# BLDC_Controller.net
KiCad netlist of a schematic drawn in EAGLE
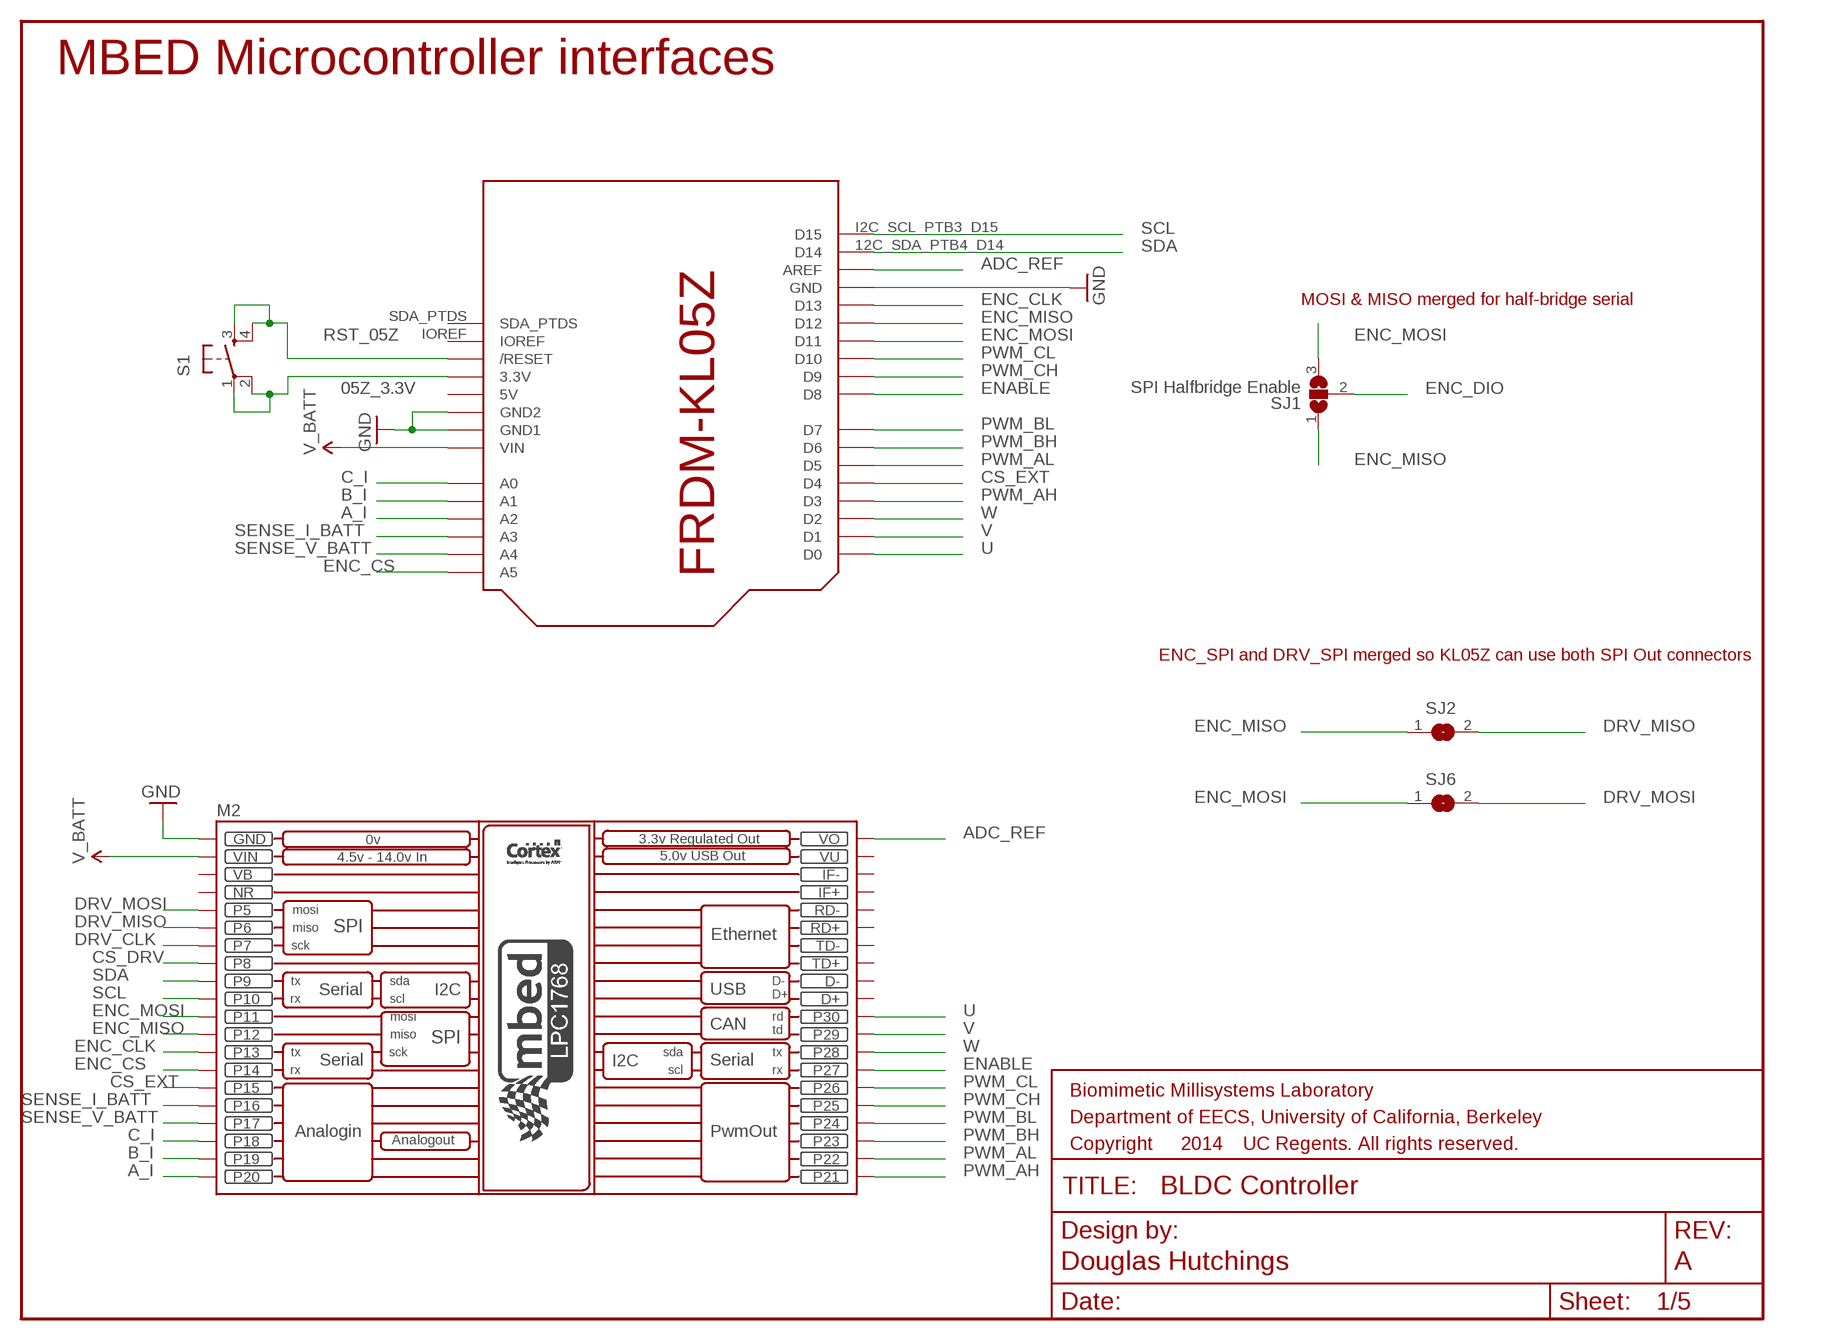
[diagram p0: schematic, sheet 1]
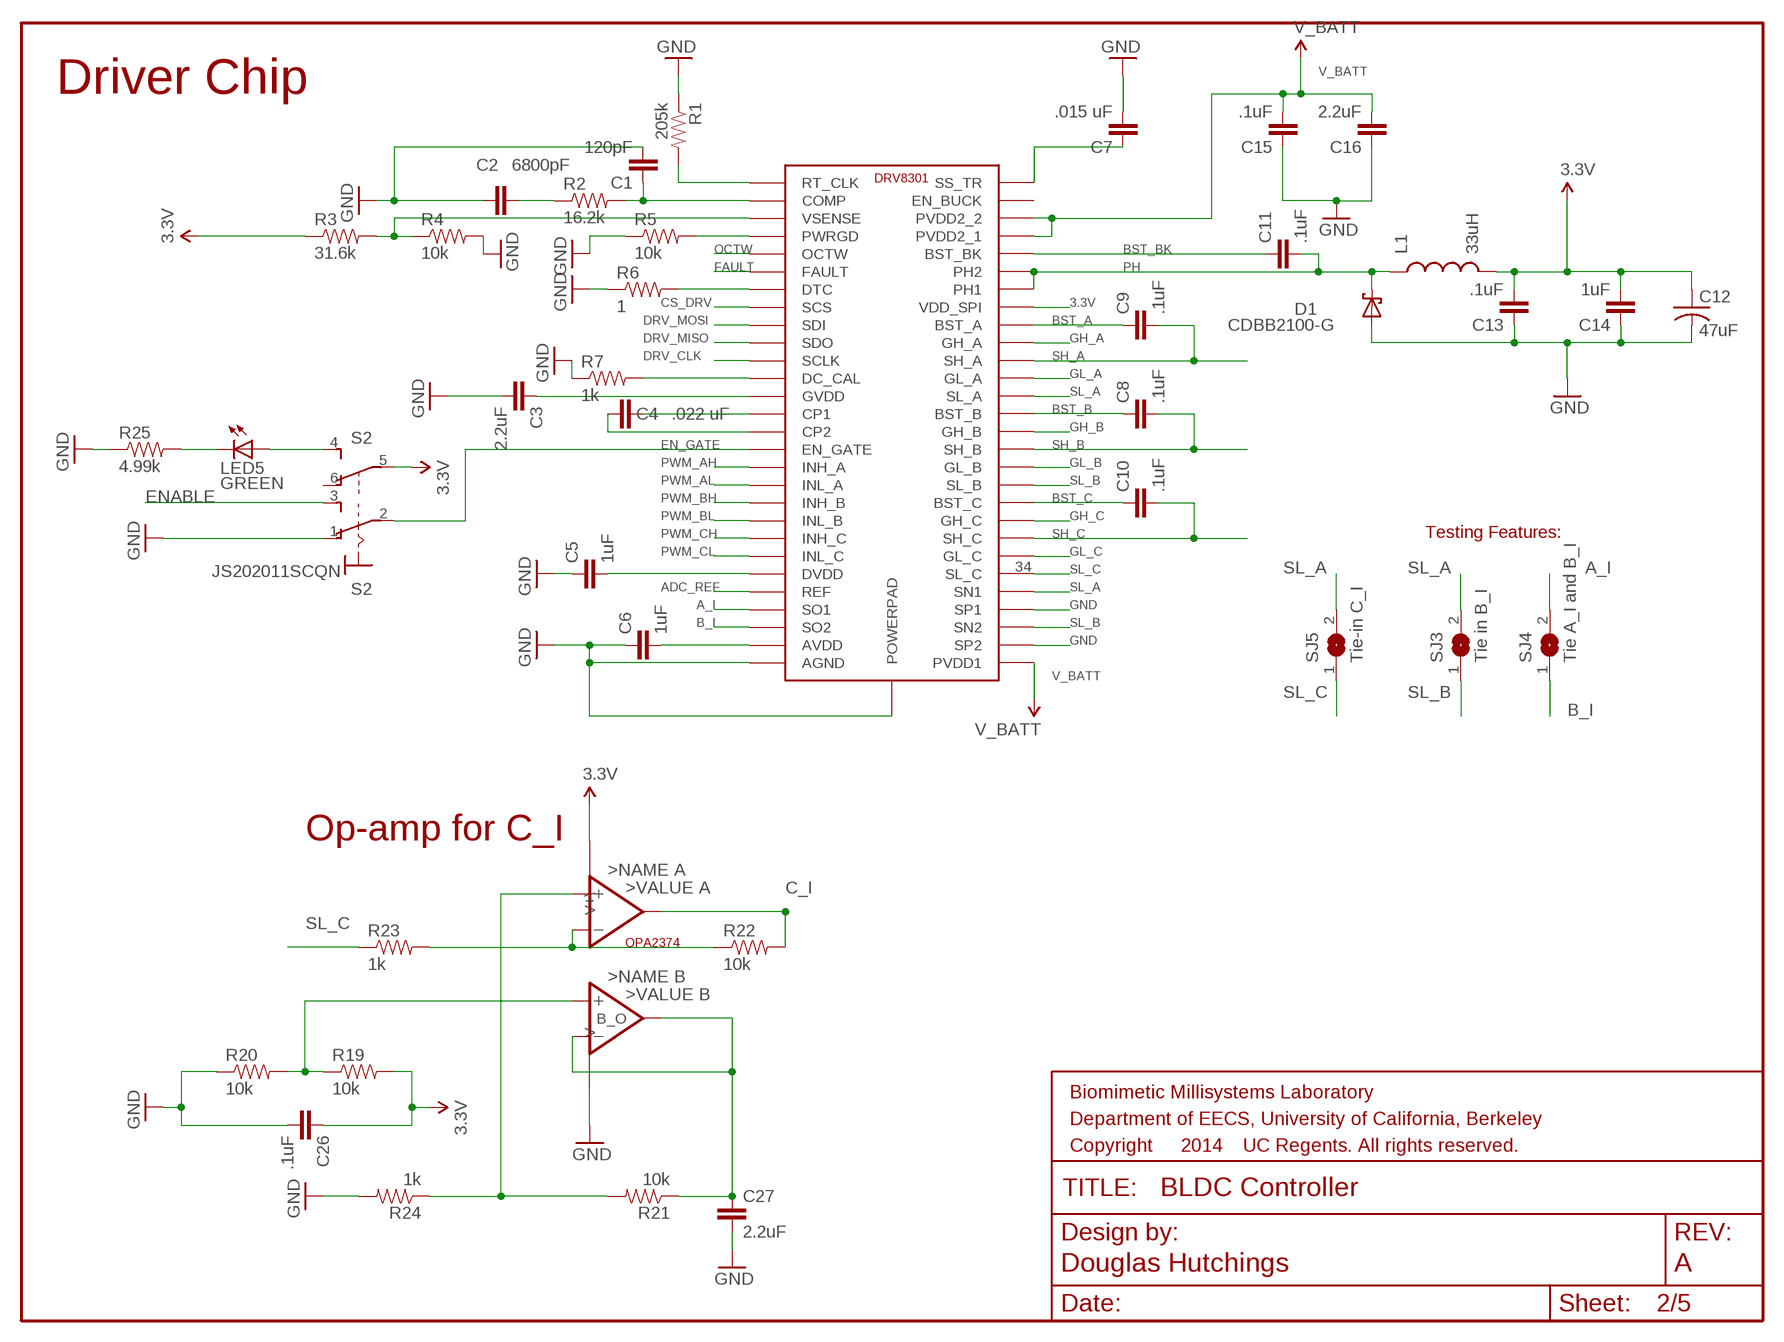
[diagram p1: schematic, sheet 2]
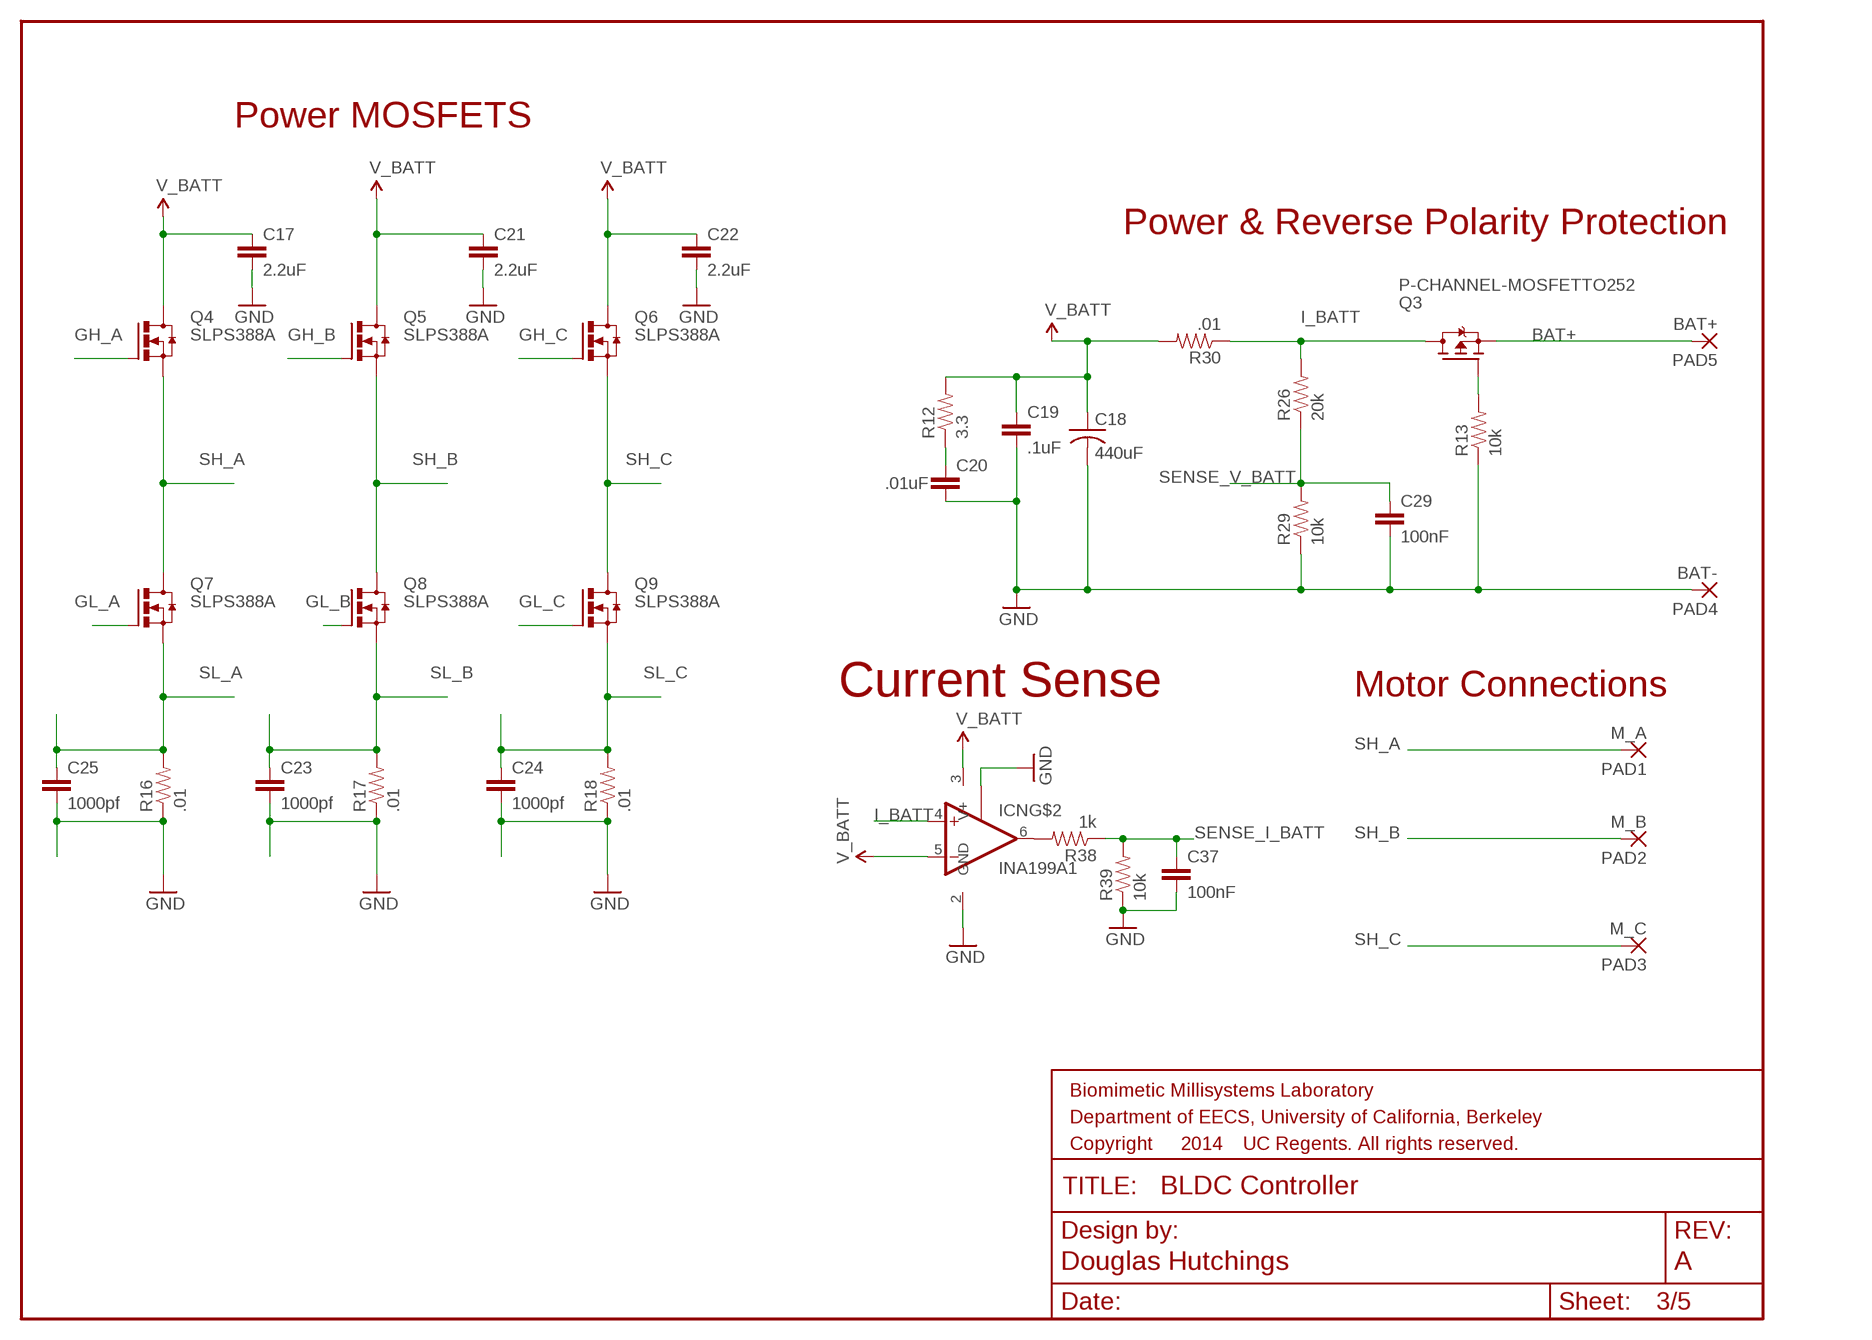
[diagram p2: schematic, sheet 3]
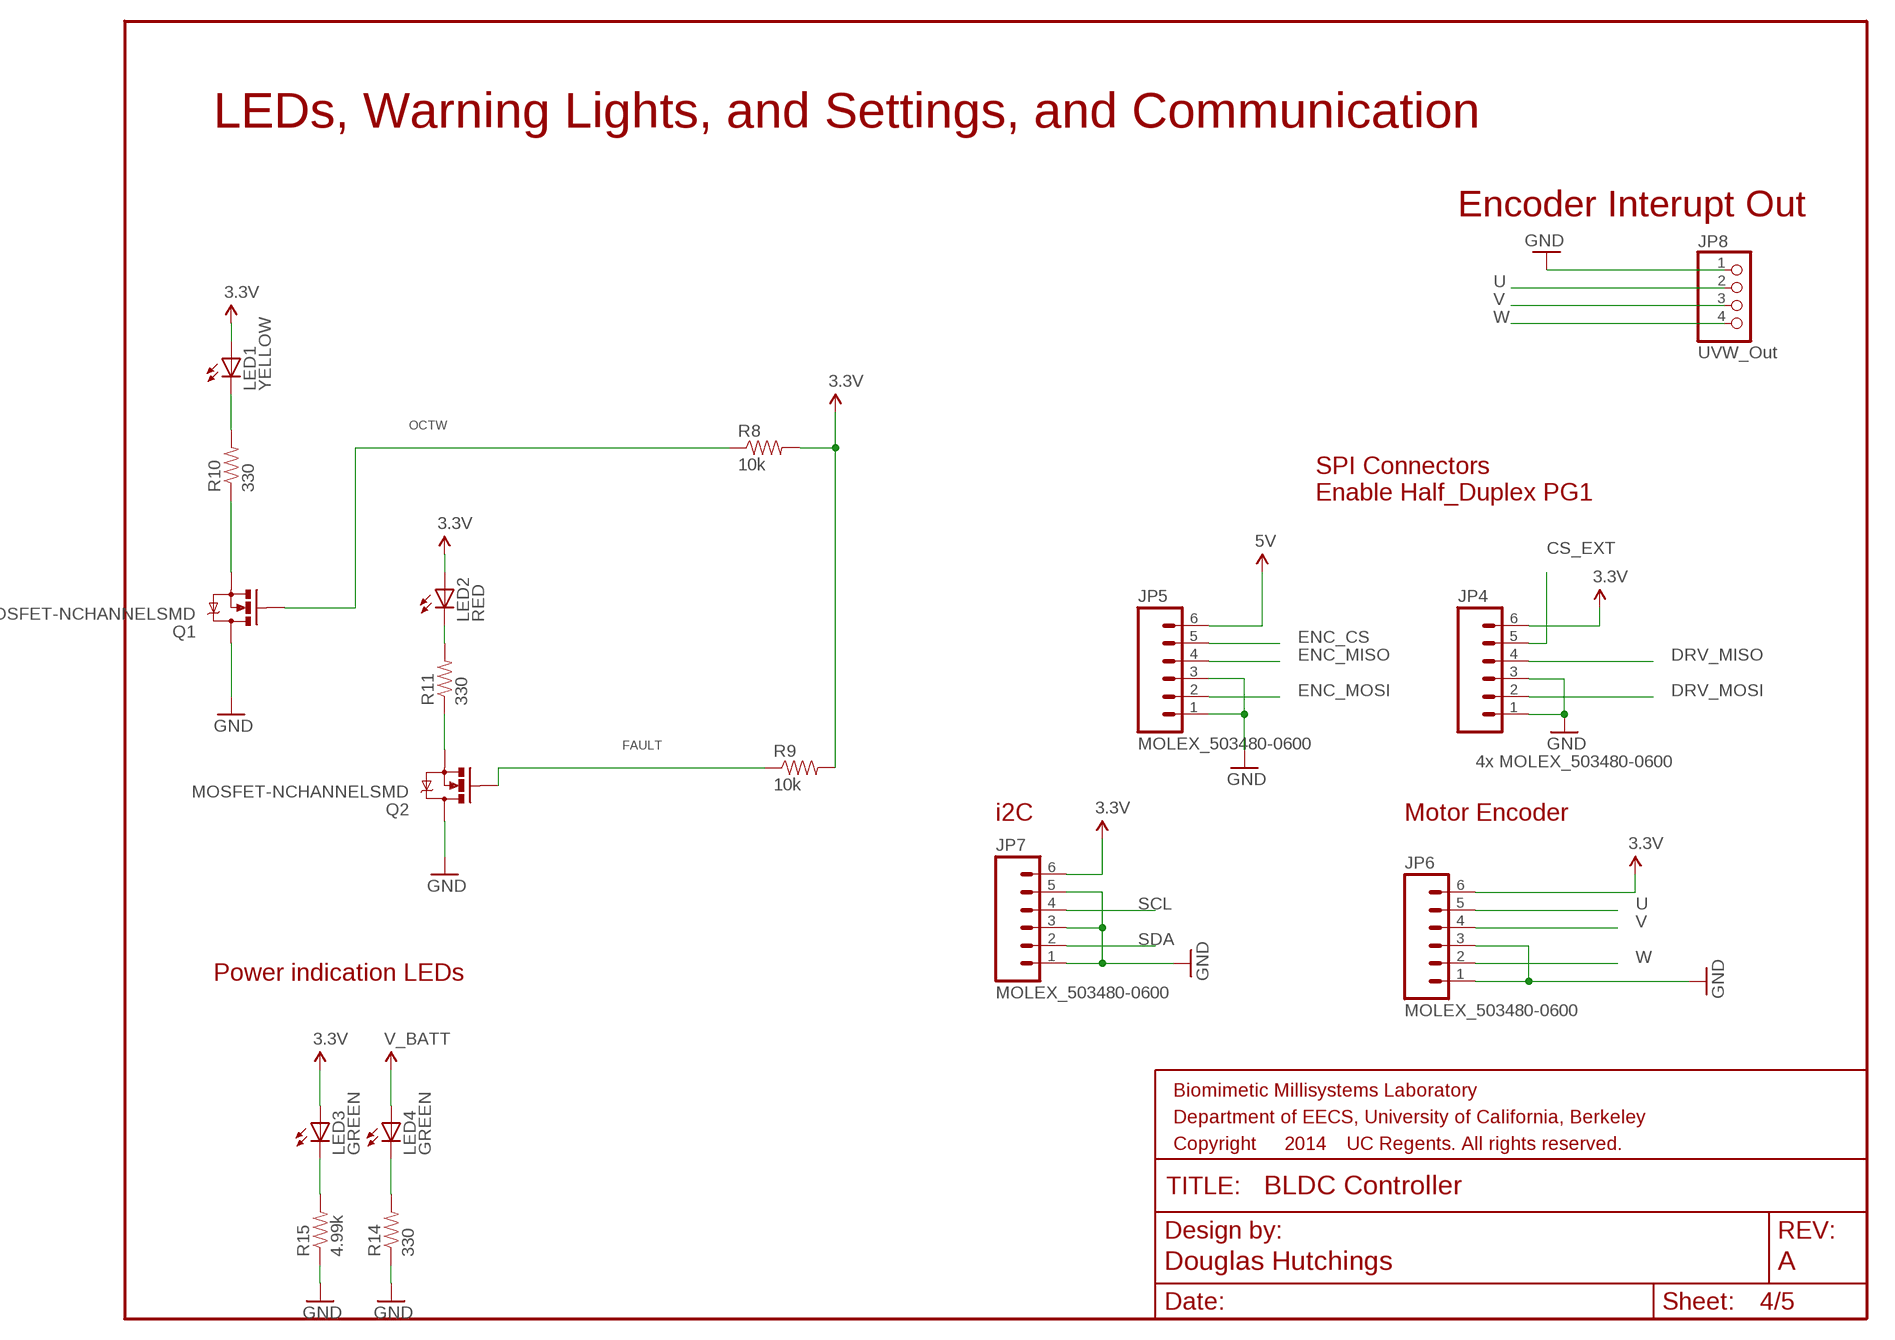
[diagram p3: schematic, sheet 4]
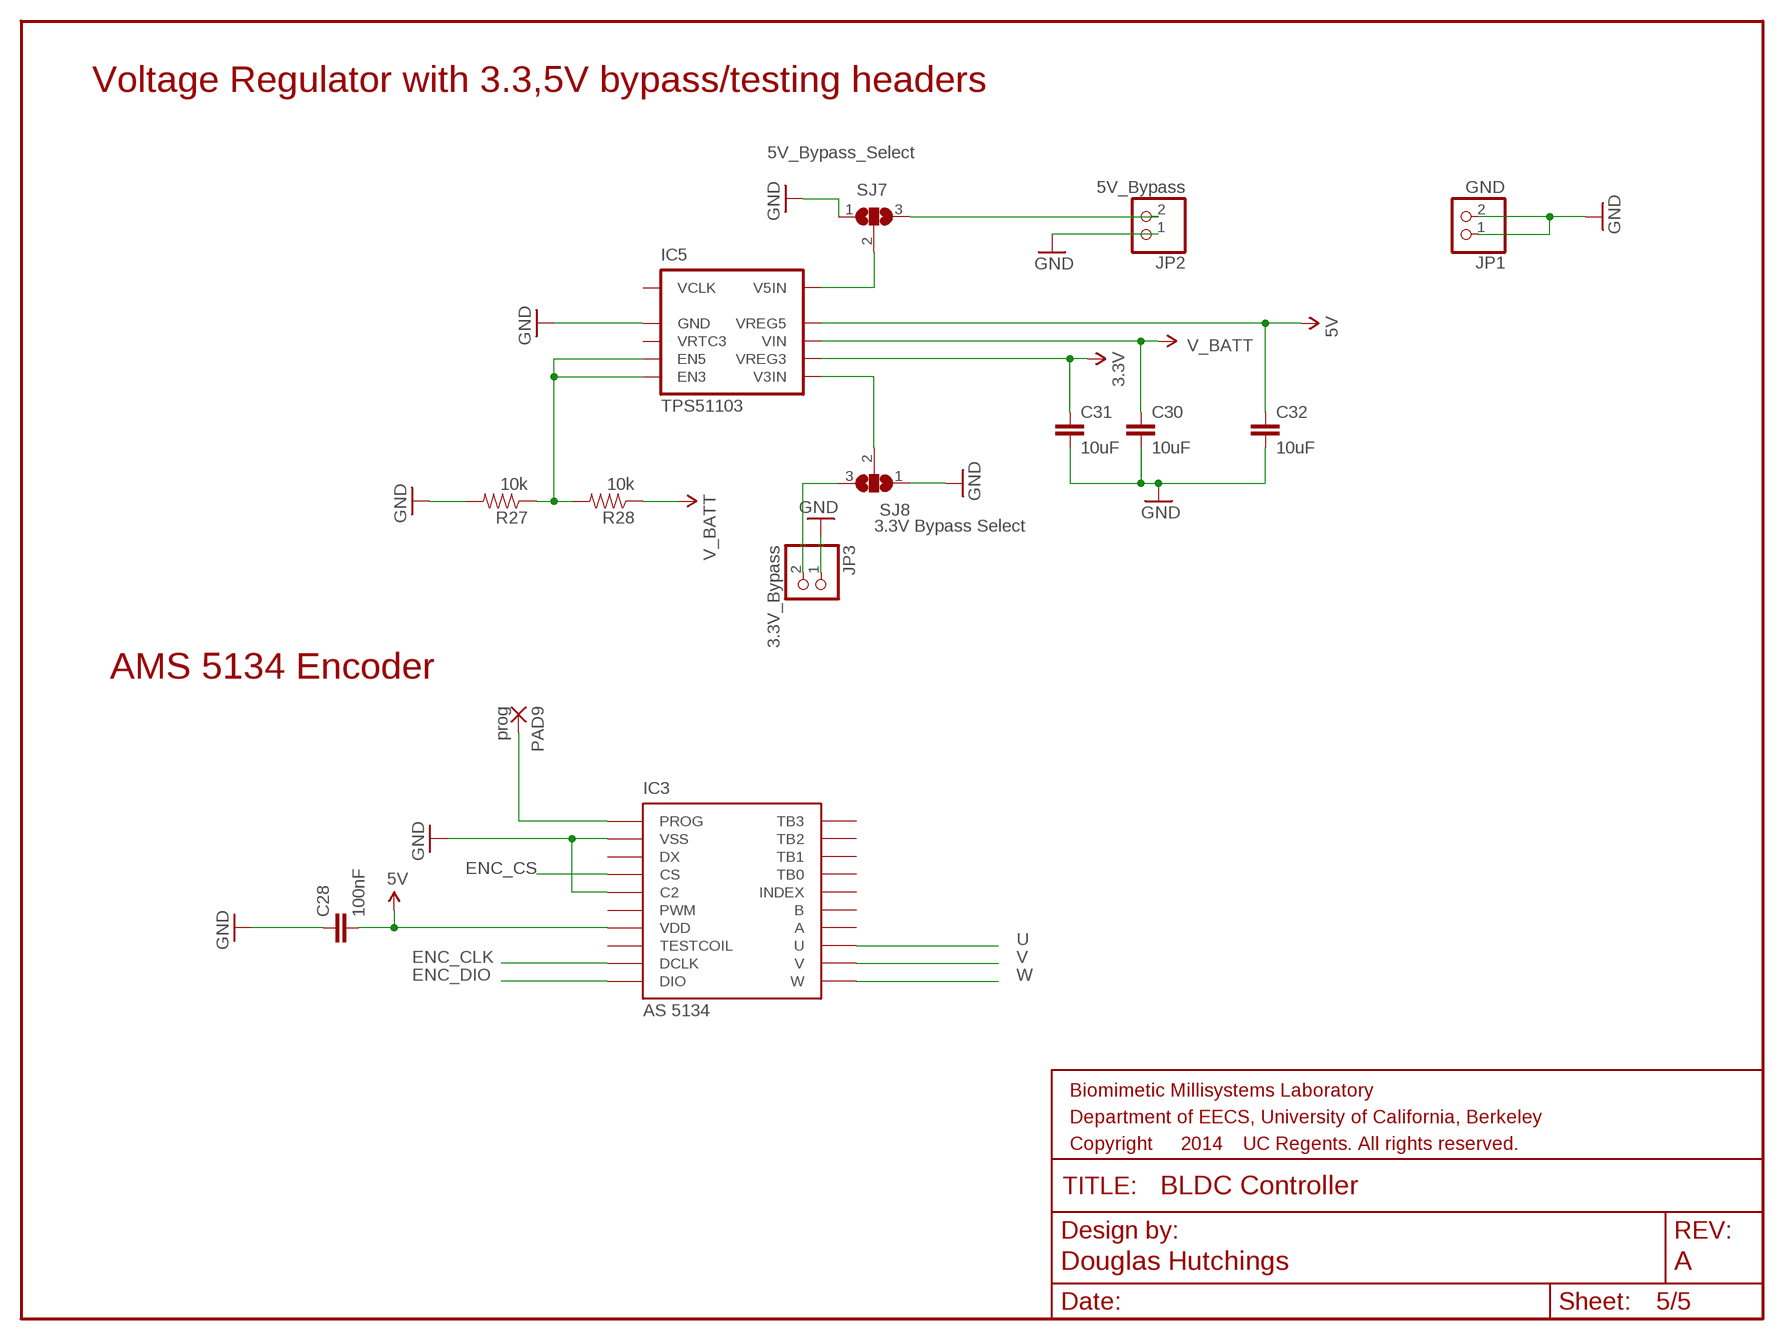
[diagram p4: schematic, sheet 5]

(export (version "E")
  (design (tool "Eeschema 10.0.6"))
  (components
    (comp (ref "M1")
      (value "FRDM-KL05Z")
      (footprint "eagle-import:FREESCALEKL05Z")
      (libsource (lib "eagle-import") (part "FRDM-KL05Z"))
    )
    (comp (ref "M2")
      (value "MBED_NXP_LPC1768")
      (footprint "eagle-import:MBED-KIT")
      (libsource (lib "eagle-import") (part "MBED_NXP_LPC1768"))
    )
    (comp (ref "S1")
      (value "TAC_SWITCHPTH")
      (footprint "eagle-import:TACTILE-PTH")
      (libsource (lib "eagle-import") (part "TAC_SWITCHPTH"))
    )
    (comp (ref "SJ1")
      (value "SPI Halfbridge Enable")
      (footprint "eagle-import:SJ_2")
      (libsource (lib "eagle-import") (part "SJ2W"))
    )
    (comp (ref "SJ2") (value "SJ") (footprint "eagle-import:SJ") (libsource (lib "eagle-import") (part "SJ")))
    (comp (ref "SJ6") (value "SJ") (footprint "eagle-import:SJ") (libsource (lib "eagle-import") (part "SJ")))
    (comp (ref "C28")
      (value "100nF")
      (footprint "eagle-import:0402-CAP")
      (libsource (lib "eagle-import") (part "CAP0402-CAP"))
    )
    (comp (ref "C30")
      (value "10uF")
      (footprint "eagle-import:0603-CAP")
      (libsource (lib "eagle-import") (part "CAP0603-CAP"))
    )
    (comp (ref "C31")
      (value "10uF")
      (footprint "eagle-import:0603-CAP")
      (libsource (lib "eagle-import") (part "CAP0603-CAP"))
    )
    (comp (ref "C32")
      (value "10uF")
      (footprint "eagle-import:0603-CAP")
      (libsource (lib "eagle-import") (part "CAP0603-CAP"))
    )
    (comp (ref "IC3")
      (value "AS 5134")
      (footprint "eagle-import:AS5134")
      (libsource (lib "eagle-import") (part "AS5134"))
    )
    (comp (ref "IC5")
      (value "TPS51103")
      (footprint "eagle-import:DRC(S-PVSON-N10)")
      (libsource (lib "eagle-import") (part "TPS51103"))
    )
    (comp (ref "JP1")
      (value "GND")
      (footprint "eagle-import:1X02")
      (libsource (lib "eagle-import") (part "PINHD-1X2"))
    )
    (comp (ref "JP2")
      (value "5V_Bypass")
      (footprint "eagle-import:1X02")
      (libsource (lib "eagle-import") (part "PINHD-1X2"))
    )
    (comp (ref "JP3")
      (value "3.3V_Bypass")
      (footprint "eagle-import:1X02")
      (libsource (lib "eagle-import") (part "PINHD-1X2"))
    )
    (comp (ref "PAD9")
      (value "prog")
      (footprint "eagle-import:SMD1,27-2,54")
      (libsource (lib "eagle-import") (part "SMD2"))
    )
    (comp (ref "R27")
      (value "10k")
      (footprint "eagle-import:0402-RES")
      (libsource (lib "eagle-import") (part "RESISTOR0402-RES"))
    )
    (comp (ref "R28")
      (value "10k")
      (footprint "eagle-import:0402-RES")
      (libsource (lib "eagle-import") (part "RESISTOR0402-RES"))
    )
    (comp (ref "SJ7")
      (value "5V_Bypass_Select")
      (footprint "eagle-import:SJ_2")
      (libsource (lib "eagle-import") (part "SJ2W"))
    )
    (comp (ref "SJ8")
      (value "3.3V Bypass Select")
      (footprint "eagle-import:SJ_2")
      (libsource (lib "eagle-import") (part "SJ2W"))
    )
    (comp (ref "C17")
      (value "2.2uF")
      (footprint "eagle-import:0603-CAP")
      (libsource (lib "eagle-import") (part "CAP0603-CAP"))
    )
    (comp (ref "C18")
      (value "440uF")
      (footprint "eagle-import:C1210")
      (libsource (lib "eagle-import") (part "C-USC1210"))
    )
    (comp (ref "C19")
      (value ".1uF")
      (footprint "eagle-import:0402-CAP")
      (libsource (lib "eagle-import") (part "CAP0402-CAP"))
    )
    (comp (ref "C20")
      (value ".01uF")
      (footprint "eagle-import:0402-CAP")
      (libsource (lib "eagle-import") (part "CAP0402-CAP"))
    )
    (comp (ref "C21")
      (value "2.2uF")
      (footprint "eagle-import:0603-CAP")
      (libsource (lib "eagle-import") (part "CAP0603-CAP"))
    )
    (comp (ref "C22")
      (value "2.2uF")
      (footprint "eagle-import:0603-CAP")
      (libsource (lib "eagle-import") (part "CAP0603-CAP"))
    )
    (comp (ref "C23")
      (value "1000pf")
      (footprint "eagle-import:0603-CAP")
      (libsource (lib "eagle-import") (part "CAP0603-CAP"))
    )
    (comp (ref "C24")
      (value "1000pf")
      (footprint "eagle-import:0603-CAP")
      (libsource (lib "eagle-import") (part "CAP0603-CAP"))
    )
    (comp (ref "C25")
      (value "1000pf")
      (footprint "eagle-import:0603-CAP")
      (libsource (lib "eagle-import") (part "CAP0603-CAP"))
    )
    (comp (ref "C29")
      (value "100nF")
      (footprint "eagle-import:0402-CAP")
      (libsource (lib "eagle-import") (part "CAP0402-CAP"))
    )
    (comp (ref "C37")
      (value "100nF")
      (footprint "eagle-import:0402-CAP")
      (libsource (lib "eagle-import") (part "CAP0402-CAP"))
    )
    (comp (ref "ICN")
      (value "INA199A1")
      (footprint "eagle-import:SC70-6")
      (libsource (lib "eagle-import") (part "INA199A1"))
    )
    (comp (ref "PAD1")
      (value "M_A")
      (footprint "eagle-import:SMD1,27-2,54")
      (libsource (lib "eagle-import") (part "SMD2"))
    )
    (comp (ref "PAD2")
      (value "M_B")
      (footprint "eagle-import:SMD1,27-2,54")
      (libsource (lib "eagle-import") (part "SMD2"))
    )
    (comp (ref "PAD3")
      (value "M_C")
      (footprint "eagle-import:SMD1,27-2,54")
      (libsource (lib "eagle-import") (part "SMD2"))
    )
    (comp (ref "PAD4")
      (value "BAT-")
      (footprint "eagle-import:SMD1,27-2,54")
      (libsource (lib "eagle-import") (part "SMD2"))
    )
    (comp (ref "PAD5")
      (value "BAT+")
      (footprint "eagle-import:SMD1,27-2,54")
      (libsource (lib "eagle-import") (part "SMD2"))
    )
    (comp (ref "Q3")
      (value "P-CHANNEL-MOSFETTO252")
      (footprint "eagle-import:TO252")
      (libsource (lib "eagle-import") (part "P-CHANNEL-MOSFETTO252"))
    )
    (comp (ref "Q4")
      (value "SLPS388A")
      (footprint "eagle-import:SLPS388A")
      (libsource (lib "eagle-import") (part "SLPS388A"))
    )
    (comp (ref "Q5")
      (value "SLPS388A")
      (footprint "eagle-import:SLPS388A")
      (libsource (lib "eagle-import") (part "SLPS388A"))
    )
    (comp (ref "Q6")
      (value "SLPS388A")
      (footprint "eagle-import:SLPS388A")
      (libsource (lib "eagle-import") (part "SLPS388A"))
    )
    (comp (ref "Q7")
      (value "SLPS388A")
      (footprint "eagle-import:SLPS388A")
      (libsource (lib "eagle-import") (part "SLPS388A"))
    )
    (comp (ref "Q8")
      (value "SLPS388A")
      (footprint "eagle-import:SLPS388A")
      (libsource (lib "eagle-import") (part "SLPS388A"))
    )
    (comp (ref "Q9")
      (value "SLPS388A")
      (footprint "eagle-import:SLPS388A")
      (libsource (lib "eagle-import") (part "SLPS388A"))
    )
    (comp (ref "R12")
      (value "3.3")
      (footprint "eagle-import:0402-RES")
      (libsource (lib "eagle-import") (part "RESISTOR0402-RES"))
    )
    (comp (ref "R13")
      (value "10k")
      (footprint "eagle-import:0603-RES")
      (libsource (lib "eagle-import") (part "RESISTOR0603-RES"))
    )
    (comp (ref "R16")
      (value ".01")
      (footprint "eagle-import:R2010")
      (libsource (lib "eagle-import") (part "RESISTOR2010"))
    )
    (comp (ref "R17")
      (value ".01")
      (footprint "eagle-import:R2010")
      (libsource (lib "eagle-import") (part "RESISTOR2010"))
    )
    (comp (ref "R18")
      (value ".01")
      (footprint "eagle-import:R2010")
      (libsource (lib "eagle-import") (part "RESISTOR2010"))
    )
    (comp (ref "R26")
      (value "20k")
      (footprint "eagle-import:0402-RES")
      (libsource (lib "eagle-import") (part "RESISTOR0402-RES"))
    )
    (comp (ref "R29")
      (value "10k")
      (footprint "eagle-import:0402-RES")
      (libsource (lib "eagle-import") (part "RESISTOR0402-RES"))
    )
    (comp (ref "R30")
      (value ".01")
      (footprint "eagle-import:R2010")
      (libsource (lib "eagle-import") (part "RESISTOR2010"))
    )
    (comp (ref "R38")
      (value "1k")
      (footprint "eagle-import:0402-RES")
      (libsource (lib "eagle-import") (part "RESISTOR0402-RES"))
    )
    (comp (ref "R39")
      (value "10k")
      (footprint "eagle-import:0402-RES")
      (libsource (lib "eagle-import") (part "RESISTOR0402-RES"))
    )
    (comp (ref "C1")
      (value "120pF")
      (footprint "eagle-import:0402-CAP")
      (libsource (lib "eagle-import") (part "CAP0402-CAP"))
    )
    (comp (ref "C2")
      (value "6800pF")
      (footprint "eagle-import:0402-CAP")
      (libsource (lib "eagle-import") (part "CAP0402-CAP"))
    )
    (comp (ref "C3")
      (value "2.2uF")
      (footprint "eagle-import:0402-CAP")
      (libsource (lib "eagle-import") (part "CAP0402-CAP"))
    )
    (comp (ref "C4")
      (value ".022 uF")
      (footprint "eagle-import:0402-CAP")
      (libsource (lib "eagle-import") (part "CAP0402-CAP"))
    )
    (comp (ref "C5")
      (value "1uF")
      (footprint "eagle-import:0402-CAP")
      (libsource (lib "eagle-import") (part "CAP0402-CAP"))
    )
    (comp (ref "C6")
      (value "1uF")
      (footprint "eagle-import:0402-CAP")
      (libsource (lib "eagle-import") (part "CAP0402-CAP"))
    )
    (comp (ref "C7")
      (value ".015 uF")
      (footprint "eagle-import:0402-CAP")
      (libsource (lib "eagle-import") (part "CAP0402-CAP"))
    )
    (comp (ref "C8")
      (value ".1uF")
      (footprint "eagle-import:0402-CAP")
      (libsource (lib "eagle-import") (part "CAP0402-CAP"))
    )
    (comp (ref "C9")
      (value ".1uF")
      (footprint "eagle-import:0402-CAP")
      (libsource (lib "eagle-import") (part "CAP0402-CAP"))
    )
    (comp (ref "C10")
      (value ".1uF")
      (footprint "eagle-import:0402-CAP")
      (libsource (lib "eagle-import") (part "CAP0402-CAP"))
    )
    (comp (ref "C11")
      (value ".1uF")
      (footprint "eagle-import:0402-CAP")
      (libsource (lib "eagle-import") (part "CAP0402-CAP"))
    )
    (comp (ref "C12")
      (value "47uF")
      (footprint "eagle-import:C0603")
      (libsource (lib "eagle-import") (part "C-USC0603"))
    )
    (comp (ref "C13")
      (value ".1uF")
      (footprint "eagle-import:0402-CAP")
      (libsource (lib "eagle-import") (part "CAP0402-CAP"))
    )
    (comp (ref "C14")
      (value "1uF")
      (footprint "eagle-import:0402-CAP")
      (libsource (lib "eagle-import") (part "CAP0402-CAP"))
    )
    (comp (ref "C15")
      (value ".1uF")
      (footprint "eagle-import:0402-CAP")
      (libsource (lib "eagle-import") (part "CAP0402-CAP"))
    )
    (comp (ref "C16")
      (value "2.2uF")
      (footprint "eagle-import:0402-CAP")
      (libsource (lib "eagle-import") (part "CAP0402-CAP"))
    )
    (comp (ref "C26")
      (value ".1uF")
      (footprint "eagle-import:0402-CAP")
      (libsource (lib "eagle-import") (part "CAP0402-CAP"))
    )
    (comp (ref "C27")
      (value "2.2uF")
      (footprint "eagle-import:0402-CAP")
      (libsource (lib "eagle-import") (part "CAP0402-CAP"))
    )
    (comp (ref "D1")
      (value "CDBB2100-G")
      (footprint "eagle-import:SMB")
      (libsource (lib "eagle-import") (part "SCHOTTKY-DIODESMD"))
    )
    (comp (ref "IC1")
      (value "DRV8301")
      (footprint "eagle-import:DRV8301")
      (libsource (lib "eagle-import") (part "DRV8301"))
    )
    (comp (ref "IC2")
      (value "OPA2374")
      (footprint "eagle-import:SOT-23")
      (libsource (lib "eagle-import") (part "OPA2374"))
    )
    (comp (ref "L1")
      (value "33uH")
      (footprint "eagle-import:0805")
      (libsource (lib "eagle-import") (part "INDUCTOR0805"))
    )
    (comp (ref "LED5")
      (value "GREEN")
      (footprint "eagle-import:LED-0603")
      (libsource (lib "eagle-import") (part "LED0603"))
    )
    (comp (ref "R1")
      (value "205k")
      (footprint "eagle-import:0402-RES")
      (libsource (lib "eagle-import") (part "RESISTOR0402-RES"))
    )
    (comp (ref "R2")
      (value "16.2k")
      (footprint "eagle-import:0402-RES")
      (libsource (lib "eagle-import") (part "RESISTOR0402-RES"))
    )
    (comp (ref "R3")
      (value "31.6k")
      (footprint "eagle-import:0402-RES")
      (libsource (lib "eagle-import") (part "RESISTOR0402-RES"))
    )
    (comp (ref "R4")
      (value "10k")
      (footprint "eagle-import:0402-RES")
      (libsource (lib "eagle-import") (part "RESISTOR0402-RES"))
    )
    (comp (ref "R5")
      (value "10k")
      (footprint "eagle-import:0402-RES")
      (libsource (lib "eagle-import") (part "RESISTOR0402-RES"))
    )
    (comp (ref "R6")
      (value "1")
      (footprint "eagle-import:0402-RES")
      (libsource (lib "eagle-import") (part "RESISTOR0402-RES"))
    )
    (comp (ref "R7")
      (value "1k")
      (footprint "eagle-import:0402-RES")
      (libsource (lib "eagle-import") (part "RESISTOR0402-RES"))
    )
    (comp (ref "R19")
      (value "10k")
      (footprint "eagle-import:0402-RES")
      (libsource (lib "eagle-import") (part "RESISTOR0402-RES"))
    )
    (comp (ref "R20")
      (value "10k")
      (footprint "eagle-import:0402-RES")
      (libsource (lib "eagle-import") (part "RESISTOR0402-RES"))
    )
    (comp (ref "R21")
      (value "10k")
      (footprint "eagle-import:0402-RES")
      (libsource (lib "eagle-import") (part "RESISTOR0402-RES"))
    )
    (comp (ref "R22")
      (value "10k")
      (footprint "eagle-import:0402-RES")
      (libsource (lib "eagle-import") (part "RESISTOR0402-RES"))
    )
    (comp (ref "R23")
      (value "1k")
      (footprint "eagle-import:0402-RES")
      (libsource (lib "eagle-import") (part "RESISTOR0402-RES"))
    )
    (comp (ref "R24")
      (value "1k")
      (footprint "eagle-import:0402-RES")
      (libsource (lib "eagle-import") (part "RESISTOR0402-RES"))
    )
    (comp (ref "R25")
      (value "4.99k")
      (footprint "eagle-import:0603-RES")
      (libsource (lib "eagle-import") (part "RESISTOR0603-RES"))
    )
    (comp (ref "S2")
      (value "JS202011SCQN")
      (footprint "eagle-import:JS202011SCQN")
      (libsource (lib "eagle-import") (part "JS202011SCQN"))
    )
    (comp (ref "SJ3")
      (value "Tie in B_I")
      (footprint "eagle-import:SJ")
      (libsource (lib "eagle-import") (part "SJ"))
    )
    (comp (ref "SJ4")
      (value "Tie A_I and B_I")
      (footprint "eagle-import:SJ")
      (libsource (lib "eagle-import") (part "SJ"))
    )
    (comp (ref "SJ5")
      (value "Tie-in C_I")
      (footprint "eagle-import:SJ")
      (libsource (lib "eagle-import") (part "SJ"))
    )
    (comp (ref "JP4")
      (value "4x MOLEX_503480-0600")
      (footprint "eagle-import:MOLEX_503480-0600")
      (libsource (lib "eagle-import") (part "MOLEX_503480-0600"))
    )
    (comp (ref "JP5")
      (value "MOLEX_503480-0600")
      (footprint "eagle-import:MOLEX_503480-0600")
      (libsource (lib "eagle-import") (part "MOLEX_503480-0600"))
    )
    (comp (ref "JP6")
      (value "MOLEX_503480-0600")
      (footprint "eagle-import:MOLEX_503480-0600")
      (libsource (lib "eagle-import") (part "MOLEX_503480-0600"))
    )
    (comp (ref "JP7")
      (value "MOLEX_503480-0600")
      (footprint "eagle-import:MOLEX_503480-0600")
      (libsource (lib "eagle-import") (part "MOLEX_503480-0600"))
    )
    (comp (ref "JP8")
      (value "UVW_Out")
      (footprint "eagle-import:1X04")
      (libsource (lib "eagle-import") (part "PINHD-1X4"))
    )
    (comp (ref "LED1")
      (value "YELLOW")
      (footprint "eagle-import:LED-0603")
      (libsource (lib "eagle-import") (part "LED0603"))
    )
    (comp (ref "LED2")
      (value "RED")
      (footprint "eagle-import:LED-0603")
      (libsource (lib "eagle-import") (part "LED0603"))
    )
    (comp (ref "LED3")
      (value "GREEN")
      (footprint "eagle-import:LED-0603")
      (libsource (lib "eagle-import") (part "LED0603"))
    )
    (comp (ref "LED4")
      (value "GREEN")
      (footprint "eagle-import:LED-0603")
      (libsource (lib "eagle-import") (part "LED0603"))
    )
    (comp (ref "Q1")
      (value "MOSFET-NCHANNELSMD")
      (footprint "eagle-import:SOT23-3")
      (libsource (lib "eagle-import") (part "MOSFET-NCHANNELSMD"))
    )
    (comp (ref "Q2")
      (value "MOSFET-NCHANNELSMD")
      (footprint "eagle-import:SOT23-3")
      (libsource (lib "eagle-import") (part "MOSFET-NCHANNELSMD"))
    )
    (comp (ref "R8")
      (value "10k")
      (footprint "eagle-import:0402-RES")
      (libsource (lib "eagle-import") (part "RESISTOR0402-RES"))
    )
    (comp (ref "R9")
      (value "10k")
      (footprint "eagle-import:0402-RES")
      (libsource (lib "eagle-import") (part "RESISTOR0402-RES"))
    )
    (comp (ref "R10")
      (value "330")
      (footprint "eagle-import:0603-RES")
      (libsource (lib "eagle-import") (part "RESISTOR0603-RES"))
    )
    (comp (ref "R11")
      (value "330")
      (footprint "eagle-import:0603-RES")
      (libsource (lib "eagle-import") (part "RESISTOR0603-RES"))
    )
    (comp (ref "R14")
      (value "330")
      (footprint "eagle-import:0603-RES")
      (libsource (lib "eagle-import") (part "RESISTOR0603-RES"))
    )
    (comp (ref "R15")
      (value "4.99k")
      (footprint "eagle-import:0603-RES")
      (libsource (lib "eagle-import") (part "RESISTOR0603-RES"))
    )
  )
  (nets
    (net (code "1") (name "3.3V") (class "Default")
      (node (ref "C12") (pin "1") (pinfunction "1_1") (pintype "passive"))
      (node (ref "C13") (pin "2") (pinfunction "2_2") (pintype "passive"))
      (node (ref "C14") (pin "2") (pinfunction "2_2") (pintype "passive"))
      (node (ref "C26") (pin "1") (pinfunction "1_1") (pintype "passive"))
      (node (ref "C31") (pin "1") (pinfunction "1_1") (pintype "passive"))
      (node (ref "IC1") (pin "49") (pinfunction "VDD_SPI_49") (pintype "bidirectional"))
      (node (ref "IC2") (pin "5") (pinfunction "V+\\_5") (pintype "bidirectional"))
      (node (ref "IC5") (pin "7") (pinfunction "VREG3_7") (pintype "input"))
      (node (ref "JP4") (pin "6") (pinfunction "6_6") (pintype "passive"))
      (node (ref "JP6") (pin "6") (pinfunction "6_6") (pintype "passive"))
      (node (ref "JP7") (pin "6") (pinfunction "6_6") (pintype "passive"))
      (node (ref "L1") (pin "2") (pinfunction "2_2") (pintype "passive"))
      (node (ref "LED1") (pin "A") (pinfunction "A_A") (pintype "passive"))
      (node (ref "LED2") (pin "A") (pinfunction "A_A") (pintype "passive"))
      (node (ref "LED3") (pin "A") (pinfunction "A_A") (pintype "passive"))
      (node (ref "R19") (pin "2") (pinfunction "2_2") (pintype "passive"))
      (node (ref "R3") (pin "1") (pinfunction "1_1") (pintype "passive"))
      (node (ref "R8") (pin "2") (pinfunction "2_2") (pintype "passive"))
      (node (ref "R9") (pin "2") (pinfunction "2_2") (pintype "passive"))
      (node (ref "S2") (pin "5") (pinfunction "P_5") (pintype "passive"))
    )
    (net (code "2") (name "5V") (class "Default")
      (node (ref "C28") (pin "2") (pinfunction "2_2") (pintype "passive"))
      (node (ref "C32") (pin "1") (pinfunction "1_1") (pintype "passive"))
      (node (ref "IC3") (pin "7") (pinfunction "VDD_7") (pintype "power_in"))
      (node (ref "IC5") (pin "9") (pinfunction "VREG5_9") (pintype "input"))
      (node (ref "JP5") (pin "6") (pinfunction "6_6") (pintype "passive"))
    )
    (net (code "3") (name "05Z_3.3V") (class "Default")
      (node (ref "M1") (pin "3.3V") (pinfunction "3.3V_3.3V") (pintype "output"))
      (node (ref "S1") (pin "1") (pinfunction "1_1") (pintype "passive"))
      (node (ref "S1") (pin "2") (pinfunction "2_2") (pintype "passive"))
    )
    (net (code "4") (name "ADC_REF") (class "Default")
      (node (ref "IC1") (pin "24") (pinfunction "REF_24") (pintype "bidirectional"))
      (node (ref "M1") (pin "AVDD") (pinfunction "AREF_AVDD") (pintype "bidirectional"))
      (node (ref "M2") (pin "VOUT") (pinfunction "VO_VOUT") (pintype "output"))
    )
    (net (code "5") (name "A_I") (class "Default")
      (node (ref "IC1") (pin "25") (pinfunction "SO1_25") (pintype "bidirectional"))
      (node (ref "M1") (pin "A2_PTA8") (pinfunction "A2_A2_PTA8") (pintype "bidirectional"))
      (node (ref "M2") (pin "P$20") (pinfunction "P20_P$20") (pintype "bidirectional"))
      (node (ref "SJ4") (pin "2") (pinfunction "2_2") (pintype "passive"))
    )
    (net (code "6") (name "BAT+") (class "Default")
      (node (ref "PAD5") (pin "1") (pinfunction "P_1") (pintype "passive"))
      (node (ref "Q3") (pin "2") (pinfunction "S_2") (pintype "passive"))
    )
    (net (code "7") (name "BST_A") (class "Default")
      (node (ref "C9") (pin "1") (pinfunction "1_1") (pintype "passive"))
      (node (ref "IC1") (pin "48") (pinfunction "BST_A_48") (pintype "bidirectional"))
    )
    (net (code "8") (name "BST_B") (class "Default")
      (node (ref "C8") (pin "1") (pinfunction "1_1") (pintype "passive"))
      (node (ref "IC1") (pin "43") (pinfunction "BST_B_43") (pintype "bidirectional"))
    )
    (net (code "9") (name "BST_BK") (class "Default")
      (node (ref "C11") (pin "1") (pinfunction "1_1") (pintype "passive"))
      (node (ref "IC1") (pin "52") (pinfunction "BST_BK_52") (pintype "bidirectional"))
    )
    (net (code "10") (name "BST_C") (class "Default")
      (node (ref "C10") (pin "1") (pinfunction "1_1") (pintype "passive"))
      (node (ref "IC1") (pin "38") (pinfunction "BST_C_38") (pintype "bidirectional"))
    )
    (net (code "11") (name "B_I") (class "Default")
      (node (ref "IC1") (pin "26") (pinfunction "SO2_26") (pintype "bidirectional"))
      (node (ref "M1") (pin "A1_PTB9") (pinfunction "A1_A1_PTB9") (pintype "bidirectional"))
      (node (ref "M2") (pin "P$19") (pinfunction "P19_P$19") (pintype "bidirectional"))
      (node (ref "SJ4") (pin "1") (pinfunction "1_1") (pintype "passive"))
    )
    (net (code "12") (name "CS_DRV") (class "Default")
      (node (ref "IC1") (pin "8") (pinfunction "SCS_8") (pintype "bidirectional"))
      (node (ref "M2") (pin "P$8") (pinfunction "P8_P$8") (pintype "bidirectional"))
    )
    (net (code "13") (name "CS_EXT") (class "Default")
      (node (ref "JP4") (pin "5") (pinfunction "5_5") (pintype "passive"))
      (node (ref "M1") (pin "PTA10_D4") (pinfunction "D4_PTA10_D4") (pintype "bidirectional"))
      (node (ref "M2") (pin "P$15") (pinfunction "P15_P$15") (pintype "bidirectional"))
    )
    (net (code "14") (name "C_I") (class "Default")
      (node (ref "IC2") (pin "1") (pinfunction "A_O_1") (pintype "bidirectional"))
      (node (ref "M1") (pin "A0_PTB8") (pinfunction "A0_A0_PTB8") (pintype "bidirectional"))
      (node (ref "M2") (pin "P$18") (pinfunction "P18_P$18") (pintype "bidirectional"))
      (node (ref "R22") (pin "2") (pinfunction "2_2") (pintype "passive"))
    )
    (net (code "15") (name "DRV_CLK") (class "Default")
      (node (ref "IC1") (pin "11") (pinfunction "SCLK_11") (pintype "bidirectional"))
      (node (ref "M2") (pin "P$7") (pinfunction "P7_P$7") (pintype "bidirectional"))
    )
    (net (code "16") (name "DRV_MISO") (class "Default")
      (node (ref "IC1") (pin "10") (pinfunction "SDO_10") (pintype "bidirectional"))
      (node (ref "JP4") (pin "4") (pinfunction "4_4") (pintype "passive"))
      (node (ref "M2") (pin "P$6") (pinfunction "P6_P$6") (pintype "bidirectional"))
      (node (ref "SJ2") (pin "2") (pinfunction "2_2") (pintype "passive"))
    )
    (net (code "17") (name "DRV_MOSI") (class "Default")
      (node (ref "IC1") (pin "9") (pinfunction "SDI_9") (pintype "bidirectional"))
      (node (ref "JP4") (pin "2") (pinfunction "2_2") (pintype "passive"))
      (node (ref "M2") (pin "P$5") (pinfunction "P5_P$5") (pintype "bidirectional"))
      (node (ref "SJ6") (pin "2") (pinfunction "2_2") (pintype "passive"))
    )
    (net (code "18") (name "ENABLE") (class "Default")
      (node (ref "M1") (pin "PTB10_D8") (pinfunction "D8_PTB10_D8") (pintype "bidirectional"))
      (node (ref "M2") (pin "P$27") (pinfunction "P27_P$27") (pintype "bidirectional"))
      (node (ref "S2") (pin "3") (pinfunction "S_3") (pintype "passive"))
    )
    (net (code "19") (name "ENC_CLK") (class "Default")
      (node (ref "IC3") (pin "9") (pinfunction "DCLK_9") (pintype "input"))
      (node (ref "M1") (pin "SCK_PTB0_D13") (pinfunction "D13_SCK_PTB0_D13") (pintype "bidirectional"))
      (node (ref "M2") (pin "P$13") (pinfunction "P13_P$13") (pintype "bidirectional"))
    )
    (net (code "20") (name "ENC_CS") (class "Default")
      (node (ref "IC3") (pin "4") (pinfunction "CS_4") (pintype "input"))
      (node (ref "JP5") (pin "5") (pinfunction "5_5") (pintype "passive"))
      (node (ref "M1") (pin "A5_PTB13") (pinfunction "A5_A5_PTB13") (pintype "bidirectional"))
      (node (ref "M2") (pin "P$14") (pinfunction "P14_P$14") (pintype "bidirectional"))
    )
    (net (code "21") (name "ENC_DIO") (class "Default")
      (node (ref "IC3") (pin "10") (pinfunction "DIO_10") (pintype "bidirectional"))
      (node (ref "SJ1") (pin "2") (pinfunction "2_2") (pintype "passive"))
    )
    (net (code "22") (name "ENC_MISO") (class "Default")
      (node (ref "JP5") (pin "4") (pinfunction "4_4") (pintype "passive"))
      (node (ref "M1") (pin "MISO_PTA6_D12") (pinfunction "D12_MISO_PTA6_D12") (pintype "bidirectional"))
      (node (ref "M2") (pin "P$12") (pinfunction "P12_P$12") (pintype "bidirectional"))
      (node (ref "SJ1") (pin "1") (pinfunction "1_1") (pintype "passive"))
      (node (ref "SJ2") (pin "1") (pinfunction "1_1") (pintype "passive"))
    )
    (net (code "23") (name "ENC_MOSI") (class "Default")
      (node (ref "JP5") (pin "2") (pinfunction "2_2") (pintype "passive"))
      (node (ref "M1") (pin "MOSI_PTA_D11") (pinfunction "D11_MOSI_PTA_D11") (pintype "bidirectional"))
      (node (ref "M2") (pin "P$11") (pinfunction "P11_P$11") (pintype "bidirectional"))
      (node (ref "SJ1") (pin "3") (pinfunction "3_3") (pintype "passive"))
      (node (ref "SJ6") (pin "1") (pinfunction "1_1") (pintype "passive"))
    )
    (net (code "24") (name "EN_GATE") (class "Default")
      (node (ref "IC1") (pin "16") (pinfunction "EN_GATE_16") (pintype "bidirectional"))
      (node (ref "S2") (pin "2") (pinfunction "P_2") (pintype "passive"))
    )
    (net (code "25") (name "FAULT") (class "Default")
      (node (ref "IC1") (pin "6") (pinfunction "FAULT_6") (pintype "bidirectional"))
      (node (ref "Q2") (pin "1") (pinfunction "G_1") (pintype "passive"))
      (node (ref "R9") (pin "1") (pinfunction "1_1") (pintype "passive"))
    )
    (net (code "26") (name "GH_A") (class "Default")
      (node (ref "IC1") (pin "47") (pinfunction "GH_A_47") (pintype "bidirectional"))
      (node (ref "Q4") (pin "4") (pinfunction "G_4") (pintype "passive"))
    )
    (net (code "27") (name "GH_B") (class "Default")
      (node (ref "IC1") (pin "42") (pinfunction "GH_B_42") (pintype "bidirectional"))
      (node (ref "Q5") (pin "4") (pinfunction "G_4") (pintype "passive"))
    )
    (net (code "28") (name "GH_C") (class "Default")
      (node (ref "IC1") (pin "37") (pinfunction "GH_C_37") (pintype "bidirectional"))
      (node (ref "Q6") (pin "4") (pinfunction "G_4") (pintype "passive"))
    )
    (net (code "29") (name "GL_A") (class "Default")
      (node (ref "IC1") (pin "45") (pinfunction "GL_A_45") (pintype "bidirectional"))
      (node (ref "Q7") (pin "4") (pinfunction "G_4") (pintype "passive"))
    )
    (net (code "30") (name "GL_B") (class "Default")
      (node (ref "IC1") (pin "40") (pinfunction "GL_B_40") (pintype "bidirectional"))
      (node (ref "Q8") (pin "4") (pinfunction "G_4") (pintype "passive"))
    )
    (net (code "31") (name "GL_C") (class "Default")
      (node (ref "IC1") (pin "35") (pinfunction "GL_C_35") (pintype "bidirectional"))
      (node (ref "Q9") (pin "4") (pinfunction "G_4") (pintype "passive"))
    )
    (net (code "32") (name "GND") (class "Default")
      (node (ref "C1") (pin "2") (pinfunction "2_2") (pintype "passive"))
      (node (ref "C12") (pin "2") (pinfunction "2_2") (pintype "passive"))
      (node (ref "C13") (pin "1") (pinfunction "1_1") (pintype "passive"))
      (node (ref "C14") (pin "1") (pinfunction "1_1") (pintype "passive"))
      (node (ref "C15") (pin "1") (pinfunction "1_1") (pintype "passive"))
      (node (ref "C16") (pin "1") (pinfunction "1_1") (pintype "passive"))
      (node (ref "C17") (pin "2") (pinfunction "2_2") (pintype "passive"))
      (node (ref "C18") (pin "2") (pinfunction "2_2") (pintype "passive"))
      (node (ref "C19") (pin "2") (pinfunction "2_2") (pintype "passive"))
      (node (ref "C2") (pin "2") (pinfunction "2_2") (pintype "passive"))
      (node (ref "C20") (pin "2") (pinfunction "2_2") (pintype "passive"))
      (node (ref "C21") (pin "2") (pinfunction "2_2") (pintype "passive"))
      (node (ref "C22") (pin "2") (pinfunction "2_2") (pintype "passive"))
      (node (ref "C23") (pin "2") (pinfunction "2_2") (pintype "passive"))
      (node (ref "C24") (pin "2") (pinfunction "2_2") (pintype "passive"))
      (node (ref "C25") (pin "2") (pinfunction "2_2") (pintype "passive"))
      (node (ref "C26") (pin "2") (pinfunction "2_2") (pintype "passive"))
      (node (ref "C27") (pin "2") (pinfunction "2_2") (pintype "passive"))
      (node (ref "C28") (pin "1") (pinfunction "1_1") (pintype "passive"))
      (node (ref "C29") (pin "2") (pinfunction "2_2") (pintype "passive"))
      (node (ref "C3") (pin "2") (pinfunction "2_2") (pintype "passive"))
      (node (ref "C30") (pin "2") (pinfunction "2_2") (pintype "passive"))
      (node (ref "C31") (pin "2") (pinfunction "2_2") (pintype "passive"))
      (node (ref "C32") (pin "2") (pinfunction "2_2") (pintype "passive"))
      (node (ref "C37") (pin "2") (pinfunction "2_2") (pintype "passive"))
      (node (ref "C5") (pin "1") (pinfunction "1_1") (pintype "passive"))
      (node (ref "C6") (pin "1") (pinfunction "1_1") (pintype "passive"))
      (node (ref "C7") (pin "2") (pinfunction "2_2") (pintype "passive"))
      (node (ref "D1") (pin "A") (pinfunction "A_A") (pintype "passive"))
      (node (ref "IC1") (pin "28") (pinfunction "AGND_28") (pintype "bidirectional"))
      (node (ref "IC1") (pin "30") (pinfunction "SP2_30") (pintype "bidirectional"))
      (node (ref "IC1") (pin "32") (pinfunction "SP1_32") (pintype "bidirectional"))
      (node (ref "IC1") (pin "EXP@1") (pinfunction "POWERPAD_EXP@1") (pintype "bidirectional"))
      (node (ref "IC1") (pin "EXP@2") (pinfunction "POWERPAD_EXP@2") (pintype "bidirectional"))
      (node (ref "IC2") (pin "4") (pinfunction "V-_4") (pintype "bidirectional"))
      (node (ref "IC3") (pin "2") (pinfunction "VSS_2") (pintype "power_in"))
      (node (ref "IC3") (pin "5") (pinfunction "C2_5") (pintype "input"))
      (node (ref "IC5") (pin "2") (pinfunction "GND_2") (pintype "bidirectional"))
      (node (ref "IC5") (pin "TH") (pinfunction "GND_TH") (pintype "bidirectional"))
      (node (ref "ICN") (pin "1") (pinfunction "REF_1") (pintype "bidirectional"))
      (node (ref "ICN") (pin "2") (pinfunction "GND_2") (pintype "power_in"))
      (node (ref "JP1") (pin "1") (pinfunction "1_1") (pintype "passive"))
      (node (ref "JP1") (pin "2") (pinfunction "2_2") (pintype "passive"))
      (node (ref "JP2") (pin "1") (pinfunction "1_1") (pintype "passive"))
      (node (ref "JP3") (pin "1") (pinfunction "1_1") (pintype "passive"))
      (node (ref "JP4") (pin "1") (pinfunction "1_1") (pintype "passive"))
      (node (ref "JP4") (pin "3") (pinfunction "3_3") (pintype "passive"))
      (node (ref "JP5") (pin "1") (pinfunction "1_1") (pintype "passive"))
      (node (ref "JP5") (pin "3") (pinfunction "3_3") (pintype "passive"))
      (node (ref "JP6") (pin "1") (pinfunction "1_1") (pintype "passive"))
      (node (ref "JP6") (pin "3") (pinfunction "3_3") (pintype "passive"))
      (node (ref "JP7") (pin "1") (pinfunction "1_1") (pintype "passive"))
      (node (ref "JP7") (pin "3") (pinfunction "3_3") (pintype "passive"))
      (node (ref "JP7") (pin "5") (pinfunction "5_5") (pintype "passive"))
      (node (ref "JP8") (pin "1") (pinfunction "1_1") (pintype "passive"))
      (node (ref "M1") (pin "GND") (pinfunction "GND_GND") (pintype "power_in"))
      (node (ref "M1") (pin "GND1") (pinfunction "GND1_GND1") (pintype "power_in"))
      (node (ref "M1") (pin "GND2") (pinfunction "GND2_GND2") (pintype "power_in"))
      (node (ref "M2") (pin "GND") (pinfunction "GND_GND") (pintype "power_in"))
      (node (ref "PAD4") (pin "1") (pinfunction "P_1") (pintype "passive"))
      (node (ref "Q1") (pin "3") (pinfunction "D_3") (pintype "passive"))
      (node (ref "Q2") (pin "3") (pinfunction "D_3") (pintype "passive"))
      (node (ref "R1") (pin "1") (pinfunction "1_1") (pintype "passive"))
      (node (ref "R13") (pin "1") (pinfunction "1_1") (pintype "passive"))
      (node (ref "R14") (pin "1") (pinfunction "1_1") (pintype "passive"))
      (node (ref "R15") (pin "1") (pinfunction "1_1") (pintype "passive"))
      (node (ref "R16") (pin "1") (pinfunction "1_1") (pintype "passive"))
      (node (ref "R17") (pin "1") (pinfunction "1_1") (pintype "passive"))
      (node (ref "R18") (pin "1") (pinfunction "1_1") (pintype "passive"))
      (node (ref "R20") (pin "1") (pinfunction "1_1") (pintype "passive"))
      (node (ref "R24") (pin "2") (pinfunction "2_2") (pintype "passive"))
      (node (ref "R25") (pin "1") (pinfunction "1_1") (pintype "passive"))
      (node (ref "R27") (pin "2") (pinfunction "2_2") (pintype "passive"))
      (node (ref "R29") (pin "1") (pinfunction "1_1") (pintype "passive"))
      (node (ref "R39") (pin "1") (pinfunction "1_1") (pintype "passive"))
      (node (ref "R4") (pin "2") (pinfunction "2_2") (pintype "passive"))
      (node (ref "R5") (pin "1") (pinfunction "1_1") (pintype "passive"))
      (node (ref "R6") (pin "1") (pinfunction "1_1") (pintype "passive"))
      (node (ref "R7") (pin "1") (pinfunction "1_1") (pintype "passive"))
      (node (ref "S2") (pin "1") (pinfunction "O_1") (pintype "passive"))
      (node (ref "SJ7") (pin "1") (pinfunction "1_1") (pintype "passive"))
      (node (ref "SJ8") (pin "1") (pinfunction "1_1") (pintype "passive"))
    )
    (net (code "33") (name "I_BATT") (class "Default")
      (node (ref "ICN") (pin "4") (pinfunction "+IN_4") (pintype "input"))
      (node (ref "Q3") (pin "3") (pinfunction "D_3") (pintype "passive"))
      (node (ref "R26") (pin "2") (pinfunction "2_2") (pintype "passive"))
      (node (ref "R30") (pin "1") (pinfunction "1_1") (pintype "passive"))
    )
    (net (code "34") (name "NR") (class "Default")
      (node (ref "M2") (pin "NR") (pinfunction "NR_NR") (pintype "power_in"))
    )
    (net (code "35") (name "Net-(C2-Pad1)") (class "Default")
      (node (ref "C2") (pin "1") (pinfunction "1_1") (pintype "passive"))
      (node (ref "R2") (pin "1") (pinfunction "1_1") (pintype "passive"))
    )
    (net (code "36") (name "Net-(C20-Pad1)") (class "Default")
      (node (ref "C20") (pin "1") (pinfunction "1_1") (pintype "passive"))
      (node (ref "R12") (pin "1") (pinfunction "1_1") (pintype "passive"))
    )
    (net (code "37") (name "Net-(IC1-AVDD)") (class "Default")
      (node (ref "C6") (pin "2") (pinfunction "2_2") (pintype "passive"))
      (node (ref "IC1") (pin "27") (pinfunction "AVDD_27") (pintype "bidirectional"))
    )
    (net (code "38") (name "Net-(IC1-COMP)") (class "Default")
      (node (ref "C1") (pin "1") (pinfunction "1_1") (pintype "passive"))
      (node (ref "IC1") (pin "2") (pinfunction "COMP_2") (pintype "bidirectional"))
      (node (ref "R2") (pin "2") (pinfunction "2_2") (pintype "passive"))
    )
    (net (code "39") (name "Net-(IC1-CP1)") (class "Default")
      (node (ref "C4") (pin "2") (pinfunction "2_2") (pintype "passive"))
      (node (ref "IC1") (pin "14") (pinfunction "CP1_14") (pintype "bidirectional"))
    )
    (net (code "40") (name "Net-(IC1-CP2)") (class "Default")
      (node (ref "C4") (pin "1") (pinfunction "1_1") (pintype "passive"))
      (node (ref "IC1") (pin "15") (pinfunction "CP2_15") (pintype "bidirectional"))
    )
    (net (code "41") (name "Net-(IC1-DC_CAL)") (class "Default")
      (node (ref "IC1") (pin "12") (pinfunction "DC_CAL_12") (pintype "bidirectional"))
      (node (ref "R7") (pin "2") (pinfunction "2_2") (pintype "passive"))
    )
    (net (code "42") (name "Net-(IC1-DTC)") (class "Default")
      (node (ref "IC1") (pin "7") (pinfunction "DTC_7") (pintype "bidirectional"))
      (node (ref "R6") (pin "2") (pinfunction "2_2") (pintype "passive"))
    )
    (net (code "43") (name "Net-(IC1-DVDD)") (class "Default")
      (node (ref "C5") (pin "2") (pinfunction "2_2") (pintype "passive"))
      (node (ref "IC1") (pin "23") (pinfunction "DVDD_23") (pintype "bidirectional"))
    )
    (net (code "44") (name "Net-(IC1-GVDD)") (class "Default")
      (node (ref "C3") (pin "1") (pinfunction "1_1") (pintype "passive"))
      (node (ref "IC1") (pin "13") (pinfunction "GVDD_13") (pintype "bidirectional"))
    )
    (net (code "45") (name "Net-(IC1-PWRGD)") (class "Default")
      (node (ref "IC1") (pin "4") (pinfunction "PWRGD_4") (pintype "bidirectional"))
      (node (ref "R5") (pin "2") (pinfunction "2_2") (pintype "passive"))
    )
    (net (code "46") (name "Net-(IC1-RT_CLK)") (class "Default")
      (node (ref "IC1") (pin "1") (pinfunction "RT_CLK_1") (pintype "bidirectional"))
      (node (ref "R1") (pin "2") (pinfunction "2_2") (pintype "passive"))
    )
    (net (code "47") (name "Net-(IC1-SS_TR)") (class "Default")
      (node (ref "C7") (pin "1") (pinfunction "1_1") (pintype "passive"))
      (node (ref "IC1") (pin "56") (pinfunction "SS_TR_56") (pintype "bidirectional"))
    )
    (net (code "48") (name "Net-(IC1-VSENSE)") (class "Default")
      (node (ref "IC1") (pin "3") (pinfunction "VSENSE_3") (pintype "bidirectional"))
      (node (ref "R3") (pin "2") (pinfunction "2_2") (pintype "passive"))
      (node (ref "R4") (pin "1") (pinfunction "1_1") (pintype "passive"))
    )
    (net (code "49") (name "Net-(IC2-A+)") (class "Default")
      (node (ref "IC2") (pin "3") (pinfunction "A+_3") (pintype "bidirectional"))
      (node (ref "R21") (pin "2") (pinfunction "2_2") (pintype "passive"))
      (node (ref "R24") (pin "1") (pinfunction "1_1") (pintype "passive"))
    )
    (net (code "50") (name "Net-(IC2-A-)") (class "Default")
      (node (ref "IC2") (pin "2") (pinfunction "A-_2") (pintype "bidirectional"))
      (node (ref "R22") (pin "1") (pinfunction "1_1") (pintype "passive"))
      (node (ref "R23") (pin "2") (pinfunction "2_2") (pintype "passive"))
    )
    (net (code "51") (name "Net-(IC2-B+)") (class "Default")
      (node (ref "IC2") (pin "8") (pinfunction "B+_8") (pintype "bidirectional"))
      (node (ref "R19") (pin "1") (pinfunction "1_1") (pintype "passive"))
      (node (ref "R20") (pin "2") (pinfunction "2_2") (pintype "passive"))
    )
    (net (code "52") (name "Net-(IC2-B-)") (class "Default")
      (node (ref "C27") (pin "1") (pinfunction "1_1") (pintype "passive"))
      (node (ref "IC2") (pin "6") (pinfunction "B_O_6") (pintype "bidirectional"))
      (node (ref "IC2") (pin "7") (pinfunction "B-_7") (pintype "bidirectional"))
      (node (ref "R21") (pin "1") (pinfunction "1_1") (pintype "passive"))
    )
    (net (code "53") (name "Net-(IC3-PROG)") (class "Default")
      (node (ref "IC3") (pin "1") (pinfunction "PROG_1") (pintype "input"))
      (node (ref "PAD9") (pin "1") (pinfunction "P_1") (pintype "passive"))
    )
    (net (code "54") (name "Net-(IC5-EN3)") (class "Default")
      (node (ref "IC5") (pin "4") (pinfunction "EN5_4") (pintype "bidirectional"))
      (node (ref "IC5") (pin "5") (pinfunction "EN3_5") (pintype "power_in"))
      (node (ref "R27") (pin "1") (pinfunction "1_1") (pintype "passive"))
      (node (ref "R28") (pin "2") (pinfunction "2_2") (pintype "passive"))
    )
    (net (code "55") (name "Net-(IC5-V3IN)") (class "Default")
      (node (ref "IC5") (pin "6") (pinfunction "V3IN_6") (pintype "input"))
      (node (ref "SJ8") (pin "2") (pinfunction "2_2") (pintype "passive"))
    )
    (net (code "56") (name "Net-(IC5-V5IN)") (class "Default")
      (node (ref "IC5") (pin "10") (pinfunction "V5IN_10") (pintype "output"))
      (node (ref "SJ7") (pin "2") (pinfunction "2_2") (pintype "passive"))
    )
    (net (code "57") (name "Net-(ICNB-OUT)") (class "Default")
      (node (ref "ICN") (pin "6") (pinfunction "OUT_6") (pintype "output"))
      (node (ref "R38") (pin "2") (pinfunction "2_2") (pintype "passive"))
    )
    (net (code "58") (name "Net-(JP2-Pad2)") (class "Default")
      (node (ref "JP2") (pin "2") (pinfunction "2_2") (pintype "passive"))
      (node (ref "SJ7") (pin "3") (pinfunction "3_3") (pintype "passive"))
    )
    (net (code "59") (name "Net-(JP3-Pad2)") (class "Default")
      (node (ref "JP3") (pin "2") (pinfunction "2_2") (pintype "passive"))
      (node (ref "SJ8") (pin "3") (pinfunction "3_3") (pintype "passive"))
    )
    (net (code "60") (name "Net-(LED1-PadC)") (class "Default")
      (node (ref "LED1") (pin "C") (pinfunction "C_C") (pintype "passive"))
      (node (ref "R10") (pin "2") (pinfunction "2_2") (pintype "passive"))
    )
    (net (code "61") (name "Net-(LED2-PadC)") (class "Default")
      (node (ref "LED2") (pin "C") (pinfunction "C_C") (pintype "passive"))
      (node (ref "R11") (pin "2") (pinfunction "2_2") (pintype "passive"))
    )
    (net (code "62") (name "Net-(LED3-PadC)") (class "Default")
      (node (ref "LED3") (pin "C") (pinfunction "C_C") (pintype "passive"))
      (node (ref "R15") (pin "2") (pinfunction "2_2") (pintype "passive"))
    )
    (net (code "63") (name "Net-(LED4-PadC)") (class "Default")
      (node (ref "LED4") (pin "C") (pinfunction "C_C") (pintype "passive"))
      (node (ref "R14") (pin "2") (pinfunction "2_2") (pintype "passive"))
    )
    (net (code "64") (name "Net-(LED5-PadC)") (class "Default")
      (node (ref "LED5") (pin "C") (pinfunction "C_C") (pintype "passive"))
      (node (ref "R25") (pin "2") (pinfunction "2_2") (pintype "passive"))
    )
    (net (code "65") (name "Net-(Q1-S)") (class "Default")
      (node (ref "Q1") (pin "2") (pinfunction "S_2") (pintype "passive"))
      (node (ref "R10") (pin "1") (pinfunction "1_1") (pintype "passive"))
    )
    (net (code "66") (name "Net-(Q2-S)") (class "Default")
      (node (ref "Q2") (pin "2") (pinfunction "S_2") (pintype "passive"))
      (node (ref "R11") (pin "1") (pinfunction "1_1") (pintype "passive"))
    )
    (net (code "67") (name "Net-(Q3-G)") (class "Default")
      (node (ref "Q3") (pin "1") (pinfunction "G_1") (pintype "passive"))
      (node (ref "R13") (pin "2") (pinfunction "2_2") (pintype "passive"))
    )
    (net (code "68") (name "Net-(S2B-S)") (class "Default")
      (node (ref "LED5") (pin "A") (pinfunction "A_A") (pintype "passive"))
      (node (ref "S2") (pin "4") (pinfunction "S_4") (pintype "passive"))
    )
    (net (code "69") (name "OCTW") (class "Default")
      (node (ref "IC1") (pin "5") (pinfunction "OCTW_5") (pintype "bidirectional"))
      (node (ref "Q1") (pin "1") (pinfunction "G_1") (pintype "passive"))
      (node (ref "R8") (pin "1") (pinfunction "1_1") (pintype "passive"))
    )
    (net (code "70") (name "PH") (class "Default")
      (node (ref "C11") (pin "2") (pinfunction "2_2") (pintype "passive"))
      (node (ref "D1") (pin "C") (pinfunction "C_C") (pintype "passive"))
      (node (ref "IC1") (pin "50") (pinfunction "PH1_50") (pintype "bidirectional"))
      (node (ref "IC1") (pin "51") (pinfunction "PH2_51") (pintype "bidirectional"))
      (node (ref "L1") (pin "1") (pinfunction "1_1") (pintype "passive"))
    )
    (net (code "71") (name "PWM_AH") (class "Default")
      (node (ref "IC1") (pin "17") (pinfunction "INH_A_17") (pintype "bidirectional"))
      (node (ref "M1") (pin "PTB5_D3") (pinfunction "D3_PTB5_D3") (pintype "bidirectional"))
      (node (ref "M2") (pin "P$21") (pinfunction "P21_P$21") (pintype "bidirectional"))
    )
    (net (code "72") (name "PWM_AL") (class "Default")
      (node (ref "IC1") (pin "18") (pinfunction "INL_A_18") (pintype "bidirectional"))
      (node (ref "M1") (pin "PTA12_D5") (pinfunction "D5_PTA12_D5") (pintype "bidirectional"))
      (node (ref "M2") (pin "P$22") (pinfunction "P22_P$22") (pintype "bidirectional"))
    )
    (net (code "73") (name "PWM_BH") (class "Default")
      (node (ref "IC1") (pin "19") (pinfunction "INH_B_19") (pintype "bidirectional"))
      (node (ref "M1") (pin "PTB6_D6") (pinfunction "D6_PTB6_D6") (pintype "bidirectional"))
      (node (ref "M2") (pin "P$23") (pinfunction "P23_P$23") (pintype "bidirectional"))
    )
    (net (code "74") (name "PWM_BL") (class "Default")
      (node (ref "IC1") (pin "20") (pinfunction "INL_B_20") (pintype "bidirectional"))
      (node (ref "M1") (pin "PTB7_D7") (pinfunction "D7_PTB7_D7") (pintype "bidirectional"))
      (node (ref "M2") (pin "P$24") (pinfunction "P24_P$24") (pintype "bidirectional"))
    )
    (net (code "75") (name "PWM_CH") (class "Default")
      (node (ref "IC1") (pin "21") (pinfunction "INH_C_21") (pintype "bidirectional"))
      (node (ref "M1") (pin "PTB11_D9") (pinfunction "D9_PTB11_D9") (pintype "bidirectional"))
      (node (ref "M2") (pin "P$25") (pinfunction "P25_P$25") (pintype "bidirectional"))
    )
    (net (code "76") (name "PWM_CL") (class "Default")
      (node (ref "IC1") (pin "22") (pinfunction "INL_C_22") (pintype "bidirectional"))
      (node (ref "M1") (pin "PTA_D10") (pinfunction "D10_PTA_D10") (pintype "bidirectional"))
      (node (ref "M2") (pin "P$26") (pinfunction "P26_P$26") (pintype "bidirectional"))
    )
    (net (code "77") (name "RST_05Z") (class "Default")
      (node (ref "M1") (pin "RESET") (pinfunction "/RESET_RESET") (pintype "bidirectional"))
      (node (ref "S1") (pin "3") (pinfunction "3_3") (pintype "passive"))
      (node (ref "S1") (pin "4") (pinfunction "4_4") (pintype "passive"))
    )
    (net (code "78") (name "SCL") (class "Default")
      (node (ref "JP7") (pin "4") (pinfunction "4_4") (pintype "passive"))
      (node (ref "M1") (pin "I2C_SCL_PTB3_D15") (pinfunction "D15_I2C_SCL_PTB3_D15") (pintype "bidirectional"))
      (node (ref "M2") (pin "P$10") (pinfunction "P10_P$10") (pintype "bidirectional"))
    )
    (net (code "79") (name "SDA") (class "Default")
      (node (ref "JP7") (pin "2") (pinfunction "2_2") (pintype "passive"))
      (node (ref "M1") (pin "12C_SDA_PTB4_D14") (pinfunction "D14_12C_SDA_PTB4_D14") (pintype "bidirectional"))
      (node (ref "M2") (pin "P$9") (pinfunction "P9_P$9") (pintype "bidirectional"))
    )
    (net (code "80") (name "SENSE_I_BATT") (class "Default")
      (node (ref "C37") (pin "1") (pinfunction "1_1") (pintype "passive"))
      (node (ref "M1") (pin "A3_PTA0") (pinfunction "A3_A3_PTA0") (pintype "bidirectional"))
      (node (ref "M2") (pin "P$16") (pinfunction "P16_P$16") (pintype "bidirectional"))
      (node (ref "R38") (pin "1") (pinfunction "1_1") (pintype "passive"))
      (node (ref "R39") (pin "2") (pinfunction "2_2") (pintype "passive"))
    )
    (net (code "81") (name "SENSE_V_BATT") (class "Default")
      (node (ref "C29") (pin "1") (pinfunction "1_1") (pintype "passive"))
      (node (ref "M1") (pin "A4_PTA9") (pinfunction "A4_A4_PTA9") (pintype "bidirectional"))
      (node (ref "M2") (pin "P$17") (pinfunction "P17_P$17") (pintype "bidirectional"))
      (node (ref "R26") (pin "1") (pinfunction "1_1") (pintype "passive"))
      (node (ref "R29") (pin "2") (pinfunction "2_2") (pintype "passive"))
    )
    (net (code "82") (name "SH_A") (class "Default")
      (node (ref "C9") (pin "2") (pinfunction "2_2") (pintype "passive"))
      (node (ref "IC1") (pin "46") (pinfunction "SH_A_46") (pintype "bidirectional"))
      (node (ref "PAD1") (pin "1") (pinfunction "P_1") (pintype "passive"))
      (node (ref "Q4") (pin "1") (pinfunction "S_1") (pintype "passive"))
      (node (ref "Q4") (pin "2") (pinfunction "S_2") (pintype "passive"))
      (node (ref "Q4") (pin "3") (pinfunction "S_3") (pintype "passive"))
      (node (ref "Q7") (pin "5") (pinfunction "D_5") (pintype "passive"))
      (node (ref "Q7") (pin "6") (pinfunction "D_6") (pintype "passive"))
      (node (ref "Q7") (pin "7") (pinfunction "D_7") (pintype "passive"))
      (node (ref "Q7") (pin "8") (pinfunction "D_8") (pintype "passive"))
      (node (ref "Q7") (pin "PAD") (pinfunction "D_PAD") (pintype "passive"))
    )
    (net (code "83") (name "SH_B") (class "Default")
      (node (ref "C8") (pin "2") (pinfunction "2_2") (pintype "passive"))
      (node (ref "IC1") (pin "41") (pinfunction "SH_B_41") (pintype "bidirectional"))
      (node (ref "PAD2") (pin "1") (pinfunction "P_1") (pintype "passive"))
      (node (ref "Q5") (pin "1") (pinfunction "S_1") (pintype "passive"))
      (node (ref "Q5") (pin "2") (pinfunction "S_2") (pintype "passive"))
      (node (ref "Q5") (pin "3") (pinfunction "S_3") (pintype "passive"))
      (node (ref "Q8") (pin "5") (pinfunction "D_5") (pintype "passive"))
      (node (ref "Q8") (pin "6") (pinfunction "D_6") (pintype "passive"))
      (node (ref "Q8") (pin "7") (pinfunction "D_7") (pintype "passive"))
      (node (ref "Q8") (pin "8") (pinfunction "D_8") (pintype "passive"))
      (node (ref "Q8") (pin "PAD") (pinfunction "D_PAD") (pintype "passive"))
    )
    (net (code "84") (name "SH_C") (class "Default")
      (node (ref "C10") (pin "2") (pinfunction "2_2") (pintype "passive"))
      (node (ref "IC1") (pin "36") (pinfunction "SH_C_36") (pintype "bidirectional"))
      (node (ref "PAD3") (pin "1") (pinfunction "P_1") (pintype "passive"))
      (node (ref "Q6") (pin "1") (pinfunction "S_1") (pintype "passive"))
      (node (ref "Q6") (pin "2") (pinfunction "S_2") (pintype "passive"))
      (node (ref "Q6") (pin "3") (pinfunction "S_3") (pintype "passive"))
      (node (ref "Q9") (pin "5") (pinfunction "D_5") (pintype "passive"))
      (node (ref "Q9") (pin "6") (pinfunction "D_6") (pintype "passive"))
      (node (ref "Q9") (pin "7") (pinfunction "D_7") (pintype "passive"))
      (node (ref "Q9") (pin "8") (pinfunction "D_8") (pintype "passive"))
      (node (ref "Q9") (pin "PAD") (pinfunction "D_PAD") (pintype "passive"))
    )
    (net (code "85") (name "SL_A") (class "Default")
      (node (ref "C25") (pin "1") (pinfunction "1_1") (pintype "passive"))
      (node (ref "IC1") (pin "33") (pinfunction "SN1_33") (pintype "bidirectional"))
      (node (ref "IC1") (pin "44") (pinfunction "SL_A_44") (pintype "bidirectional"))
      (node (ref "Q7") (pin "1") (pinfunction "S_1") (pintype "passive"))
      (node (ref "Q7") (pin "2") (pinfunction "S_2") (pintype "passive"))
      (node (ref "Q7") (pin "3") (pinfunction "S_3") (pintype "passive"))
      (node (ref "R16") (pin "2") (pinfunction "2_2") (pintype "passive"))
      (node (ref "SJ3") (pin "2") (pinfunction "2_2") (pintype "passive"))
      (node (ref "SJ5") (pin "2") (pinfunction "2_2") (pintype "passive"))
    )
    (net (code "86") (name "SL_B") (class "Default")
      (node (ref "C23") (pin "1") (pinfunction "1_1") (pintype "passive"))
      (node (ref "IC1") (pin "31") (pinfunction "SN2_31") (pintype "bidirectional"))
      (node (ref "IC1") (pin "39") (pinfunction "SL_B_39") (pintype "bidirectional"))
      (node (ref "Q8") (pin "1") (pinfunction "S_1") (pintype "passive"))
      (node (ref "Q8") (pin "2") (pinfunction "S_2") (pintype "passive"))
      (node (ref "Q8") (pin "3") (pinfunction "S_3") (pintype "passive"))
      (node (ref "R17") (pin "2") (pinfunction "2_2") (pintype "passive"))
      (node (ref "SJ3") (pin "1") (pinfunction "1_1") (pintype "passive"))
    )
    (net (code "87") (name "SL_C") (class "Default")
      (node (ref "C24") (pin "1") (pinfunction "1_1") (pintype "passive"))
      (node (ref "IC1") (pin "34") (pinfunction "SL_C_34") (pintype "bidirectional"))
      (node (ref "Q9") (pin "1") (pinfunction "S_1") (pintype "passive"))
      (node (ref "Q9") (pin "2") (pinfunction "S_2") (pintype "passive"))
      (node (ref "Q9") (pin "3") (pinfunction "S_3") (pintype "passive"))
      (node (ref "R18") (pin "2") (pinfunction "2_2") (pintype "passive"))
      (node (ref "R23") (pin "1") (pinfunction "1_1") (pintype "passive"))
      (node (ref "SJ5") (pin "1") (pinfunction "1_1") (pintype "passive"))
    )
    (net (code "88") (name "U") (class "Default")
      (node (ref "IC3") (pin "11") (pinfunction "U_11") (pintype "output"))
      (node (ref "JP6") (pin "5") (pinfunction "5_5") (pintype "passive"))
      (node (ref "JP8") (pin "2") (pinfunction "2_2") (pintype "passive"))
      (node (ref "M1") (pin "TX_PTB2_D0") (pinfunction "D0_TX_PTB2_D0") (pintype "bidirectional"))
      (node (ref "M2") (pin "P$30") (pinfunction "P30_P$30") (pintype "bidirectional"))
    )
    (net (code "89") (name "V") (class "Default")
      (node (ref "IC3") (pin "12") (pinfunction "V_12") (pintype "output"))
      (node (ref "JP6") (pin "4") (pinfunction "4_4") (pintype "passive"))
      (node (ref "JP8") (pin "3") (pinfunction "3_3") (pintype "passive"))
      (node (ref "M1") (pin "RX_PTB1_D1") (pinfunction "D1_RX_PTB1_D1") (pintype "bidirectional"))
      (node (ref "M2") (pin "P$29") (pinfunction "P29_P$29") (pintype "bidirectional"))
    )
    (net (code "90") (name "VB") (class "Default")
      (node (ref "M2") (pin "VB") (pinfunction "VB_VB") (pintype "power_in"))
    )
    (net (code "91") (name "V_BATT") (class "Default")
      (node (ref "C15") (pin "2") (pinfunction "2_2") (pintype "passive"))
      (node (ref "C16") (pin "2") (pinfunction "2_2") (pintype "passive"))
      (node (ref "C17") (pin "1") (pinfunction "1_1") (pintype "passive"))
      (node (ref "C18") (pin "1") (pinfunction "1_1") (pintype "passive"))
      (node (ref "C19") (pin "1") (pinfunction "1_1") (pintype "passive"))
      (node (ref "C21") (pin "1") (pinfunction "1_1") (pintype "passive"))
      (node (ref "C22") (pin "1") (pinfunction "1_1") (pintype "passive"))
      (node (ref "C30") (pin "1") (pinfunction "1_1") (pintype "passive"))
      (node (ref "IC1") (pin "29") (pinfunction "PVDD1_29") (pintype "bidirectional"))
      (node (ref "IC1") (pin "53") (pinfunction "PVDD2_1_53") (pintype "bidirectional"))
      (node (ref "IC1") (pin "54") (pinfunction "PVDD2_2_54") (pintype "bidirectional"))
      (node (ref "IC5") (pin "8") (pinfunction "VIN_8") (pintype "input"))
      (node (ref "ICN") (pin "3") (pinfunction "V+_3") (pintype "power_in"))
      (node (ref "ICN") (pin "5") (pinfunction "-IN_5") (pintype "input"))
      (node (ref "LED4") (pin "A") (pinfunction "A_A") (pintype "passive"))
      (node (ref "M1") (pin "VIN") (pinfunction "VIN_VIN") (pintype "power_in"))
      (node (ref "M2") (pin "VIN") (pinfunction "VIN_VIN") (pintype "power_in"))
      (node (ref "Q4") (pin "5") (pinfunction "D_5") (pintype "passive"))
      (node (ref "Q4") (pin "6") (pinfunction "D_6") (pintype "passive"))
      (node (ref "Q4") (pin "7") (pinfunction "D_7") (pintype "passive"))
      (node (ref "Q4") (pin "8") (pinfunction "D_8") (pintype "passive"))
      (node (ref "Q4") (pin "PAD") (pinfunction "D_PAD") (pintype "passive"))
      (node (ref "Q5") (pin "5") (pinfunction "D_5") (pintype "passive"))
      (node (ref "Q5") (pin "6") (pinfunction "D_6") (pintype "passive"))
      (node (ref "Q5") (pin "7") (pinfunction "D_7") (pintype "passive"))
      (node (ref "Q5") (pin "8") (pinfunction "D_8") (pintype "passive"))
      (node (ref "Q5") (pin "PAD") (pinfunction "D_PAD") (pintype "passive"))
      (node (ref "Q6") (pin "5") (pinfunction "D_5") (pintype "passive"))
      (node (ref "Q6") (pin "6") (pinfunction "D_6") (pintype "passive"))
      (node (ref "Q6") (pin "7") (pinfunction "D_7") (pintype "passive"))
      (node (ref "Q6") (pin "8") (pinfunction "D_8") (pintype "passive"))
      (node (ref "Q6") (pin "PAD") (pinfunction "D_PAD") (pintype "passive"))
      (node (ref "R12") (pin "2") (pinfunction "2_2") (pintype "passive"))
      (node (ref "R28") (pin "1") (pinfunction "1_1") (pintype "passive"))
      (node (ref "R30") (pin "2") (pinfunction "2_2") (pintype "passive"))
    )
    (net (code "92") (name "W") (class "Default")
      (node (ref "IC3") (pin "13") (pinfunction "W_13") (pintype "output"))
      (node (ref "JP6") (pin "2") (pinfunction "2_2") (pintype "passive"))
      (node (ref "JP8") (pin "4") (pinfunction "4_4") (pintype "passive"))
      (node (ref "M1") (pin "PTA11_D2") (pinfunction "D2_PTA11_D2") (pintype "bidirectional"))
      (node (ref "M2") (pin "P$28") (pinfunction "P28_P$28") (pintype "bidirectional"))
    )
    (net (code "93") (name "unconnected-(IC1-EN_BUCK-Pad55)") (class "Default")
      (node (ref "IC1") (pin "55") (pinfunction "EN_BUCK_55") (pintype "bidirectional"))
    )
    (net (code "94") (name "unconnected-(IC3-A-Pad14)") (class "Default")
      (node (ref "IC3") (pin "14") (pinfunction "A_14") (pintype "output"))
    )
    (net (code "95") (name "unconnected-(IC3-B-Pad15)") (class "Default")
      (node (ref "IC3") (pin "15") (pinfunction "B_15") (pintype "output"))
    )
    (net (code "96") (name "unconnected-(IC3-DX-Pad3)") (class "Default")
      (node (ref "IC3") (pin "3") (pinfunction "DX_3") (pintype "input"))
    )
    (net (code "97") (name "unconnected-(IC3-INDEX-Pad16)") (class "Default")
      (node (ref "IC3") (pin "16") (pinfunction "INDEX_16") (pintype "output"))
    )
    (net (code "98") (name "unconnected-(IC3-PWM-Pad6)") (class "Default")
      (node (ref "IC3") (pin "6") (pinfunction "PWM_6") (pintype "output"))
    )
    (net (code "99") (name "unconnected-(IC3-TB0-Pad17)") (class "Default")
      (node (ref "IC3") (pin "17") (pinfunction "TB0_17") (pintype "tri_state"))
    )
    (net (code "100") (name "unconnected-(IC3-TB1-Pad18)") (class "Default")
      (node (ref "IC3") (pin "18") (pinfunction "TB1_18") (pintype "tri_state"))
    )
    (net (code "101") (name "unconnected-(IC3-TB2-Pad19)") (class "Default")
      (node (ref "IC3") (pin "19") (pinfunction "TB2_19") (pintype "tri_state"))
    )
    (net (code "102") (name "unconnected-(IC3-TB3-Pad20)") (class "Default")
      (node (ref "IC3") (pin "20") (pinfunction "TB3_20") (pintype "tri_state"))
    )
    (net (code "103") (name "unconnected-(IC3-TESTCOIL-Pad8)") (class "Default")
      (node (ref "IC3") (pin "8") (pinfunction "TESTCOIL_8") (pintype "tri_state"))
    )
    (net (code "104") (name "unconnected-(IC5-VCLK-Pad1)") (class "Default")
      (node (ref "IC5") (pin "1") (pinfunction "VCLK_1") (pintype "input"))
    )
    (net (code "105") (name "unconnected-(IC5-VRTC3-Pad3)") (class "Default")
      (node (ref "IC5") (pin "3") (pinfunction "VRTC3_3") (pintype "bidirectional"))
    )
    (net (code "106") (name "unconnected-(M1-Pad5V)") (class "Default")
      (node (ref "M1") (pin "5V") (pinfunction "5V_5V") (pintype "output"))
    )
    (net (code "107") (name "unconnected-(M1-PadIOREF)") (class "Default")
      (node (ref "M1") (pin "IOREF") (pinfunction "IOREF_IOREF") (pintype "bidirectional"))
    )
    (net (code "108") (name "unconnected-(M1-PadSDA_PTDS)") (class "Default")
      (node (ref "M1") (pin "SDA_PTDS") (pinfunction "SDA_PTDS_SDA_PTDS") (pintype "bidirectional"))
    )
    (net (code "109") (name "unconnected-(M2-PadD+)") (class "Default")
      (node (ref "M2") (pin "D+") (pinfunction "D+_D+") (pintype "bidirectional"))
    )
    (net (code "110") (name "unconnected-(M2-PadD-)") (class "Default")
      (node (ref "M2") (pin "D-") (pinfunction "D-_D-") (pintype "bidirectional"))
    )
    (net (code "111") (name "unconnected-(M2-PadIF+)") (class "Default")
      (node (ref "M2") (pin "IF+") (pinfunction "IF+_IF+") (pintype "bidirectional"))
    )
    (net (code "112") (name "unconnected-(M2-PadIF-)") (class "Default")
      (node (ref "M2") (pin "IF-") (pinfunction "IF-_IF-") (pintype "bidirectional"))
    )
    (net (code "113") (name "unconnected-(M2-PadRD+)") (class "Default")
      (node (ref "M2") (pin "RD+") (pinfunction "RD+_RD+") (pintype "bidirectional"))
    )
    (net (code "114") (name "unconnected-(M2-PadRD-)") (class "Default")
      (node (ref "M2") (pin "RD-") (pinfunction "RD-_RD-") (pintype "bidirectional"))
    )
    (net (code "115") (name "unconnected-(M2-PadTD+)") (class "Default")
      (node (ref "M2") (pin "TD+") (pinfunction "TD+_TD+") (pintype "bidirectional"))
    )
    (net (code "116") (name "unconnected-(M2-PadTD-)") (class "Default")
      (node (ref "M2") (pin "TD-") (pinfunction "TD-_TD-") (pintype "bidirectional"))
    )
    (net (code "117") (name "unconnected-(M2-PadVU)") (class "Default")
      (node (ref "M2") (pin "VU") (pinfunction "VU_VU") (pintype "output"))
    )
    (net (code "118") (name "unconnected-(S2B-O-Pad6)") (class "Default")
      (node (ref "S2") (pin "6") (pinfunction "O_6") (pintype "passive"))
    )
  )
)
